# Battery_Monitoring_V4.net
KiCad netlist of a schematic drawn in EAGLE
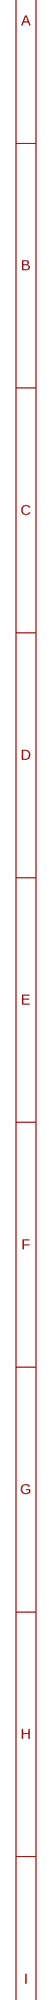
[diagram p0: schematic, sheet 1, part 1 of 2]
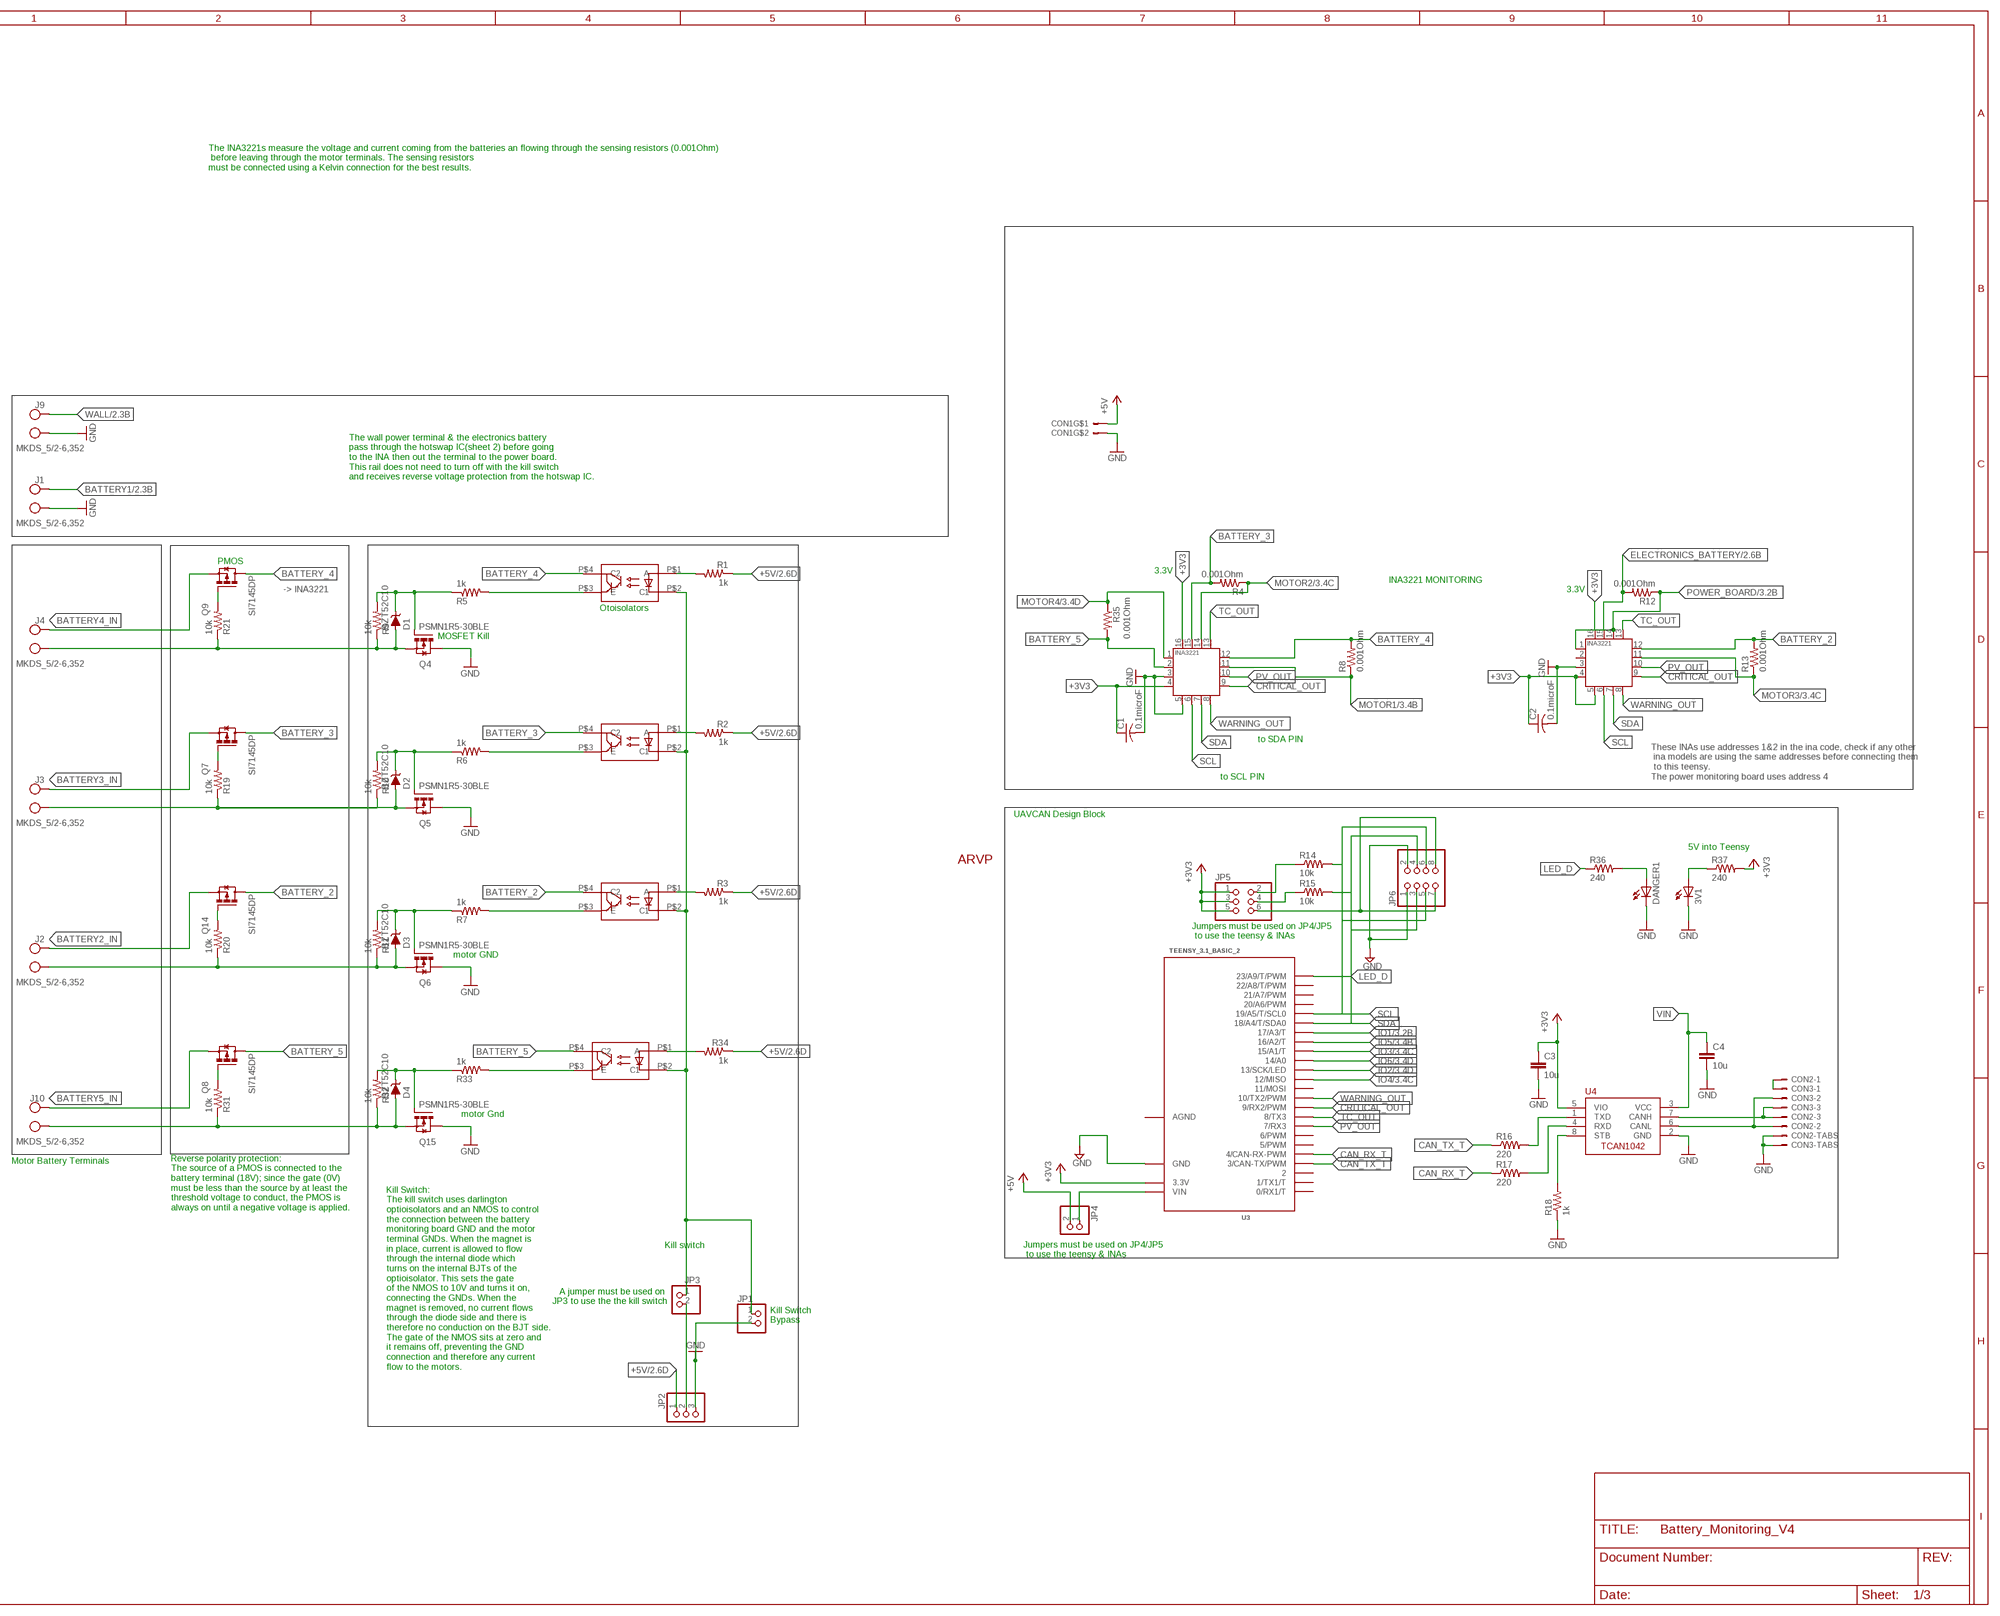
[diagram p1: schematic, sheet 1, part 2 of 2]
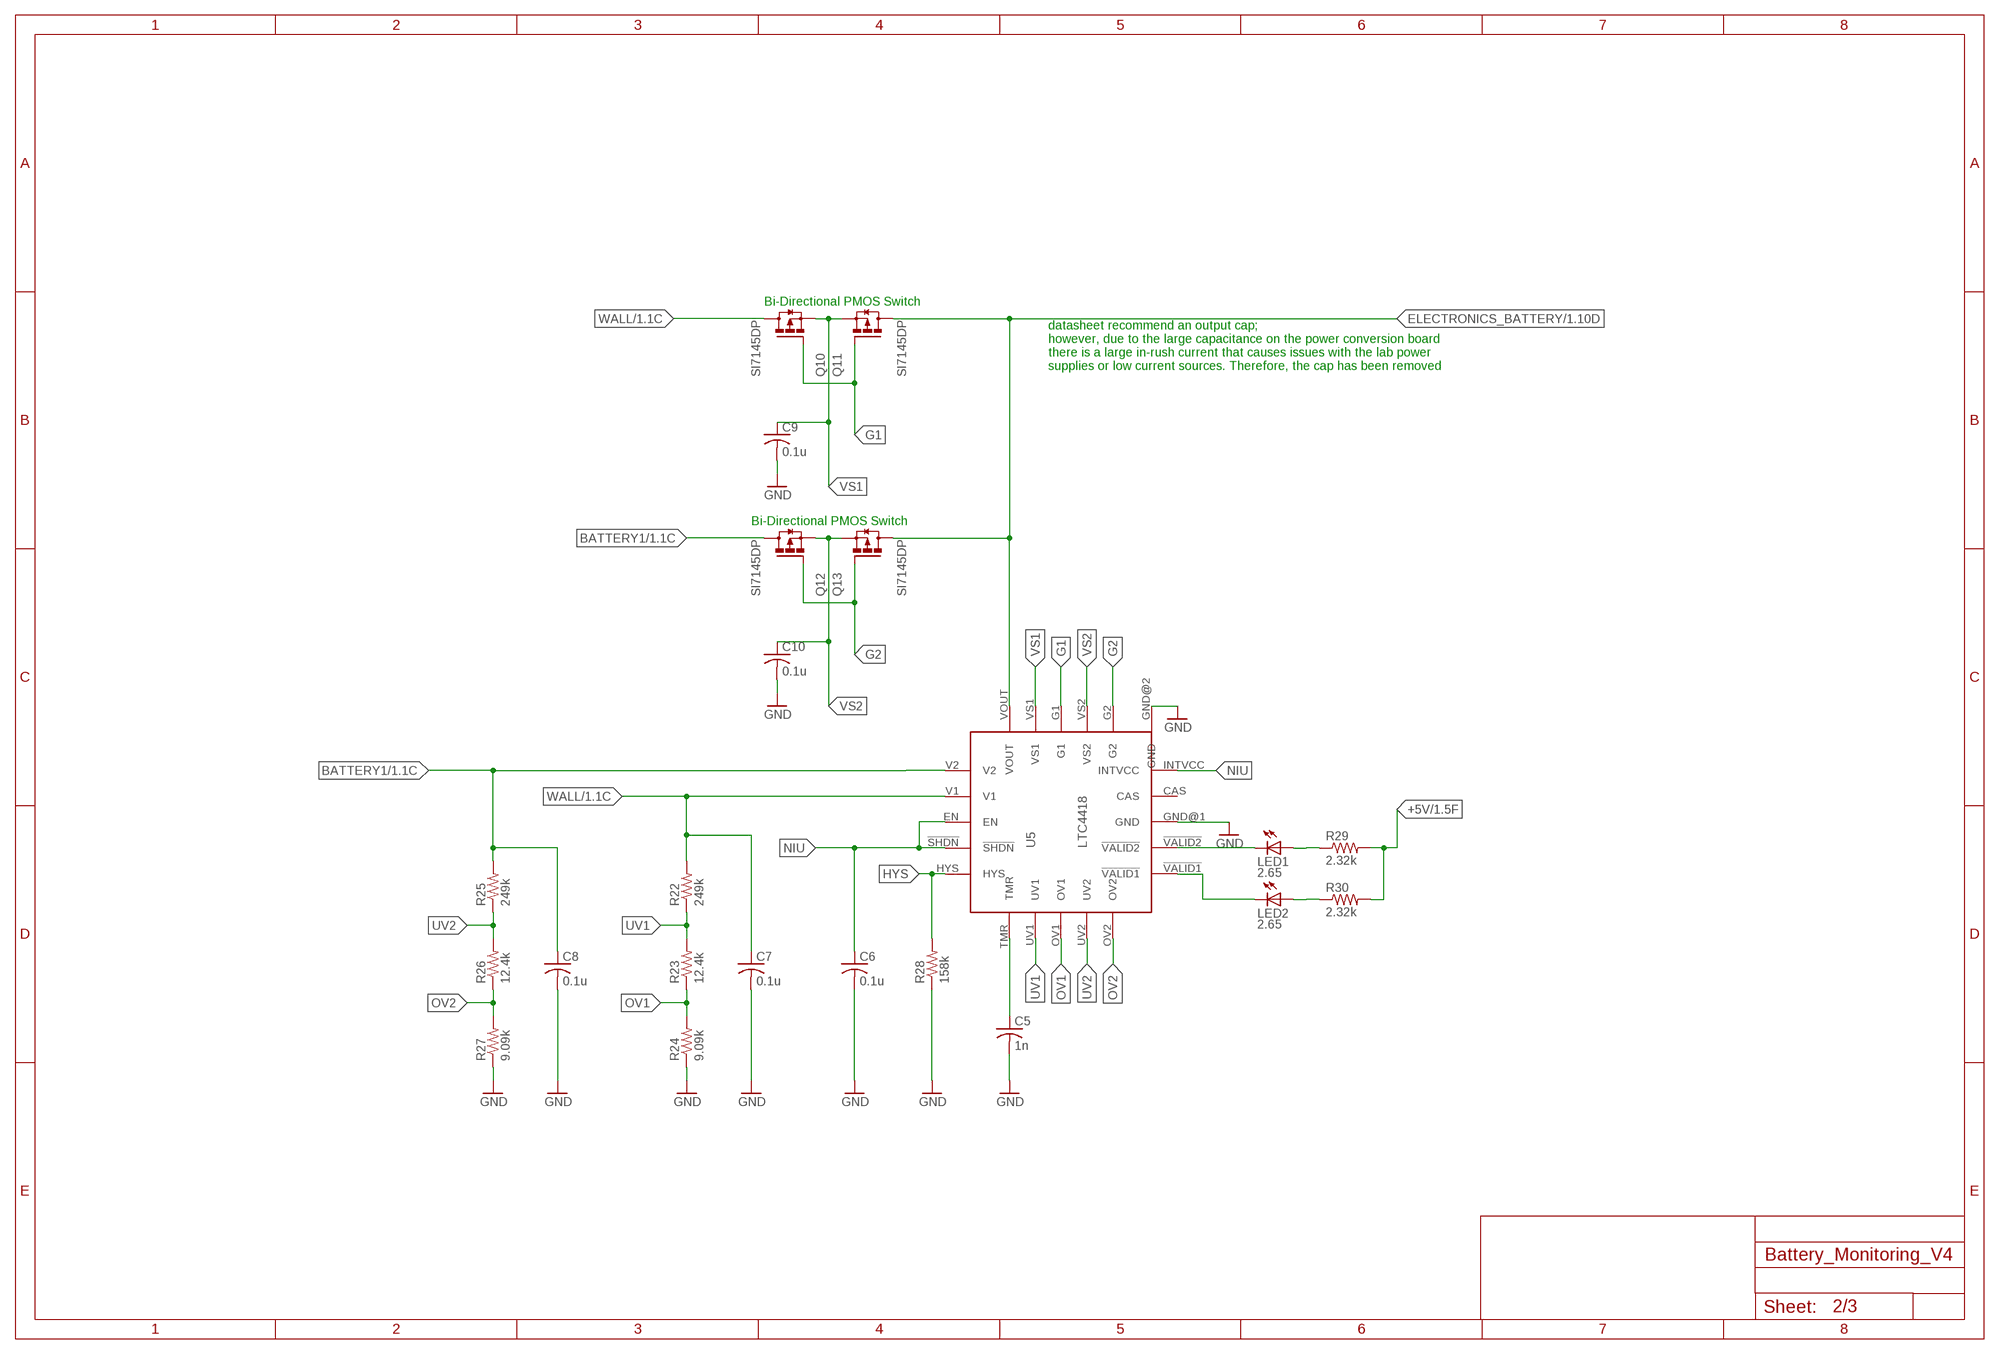
[diagram p2: schematic, sheet 2]
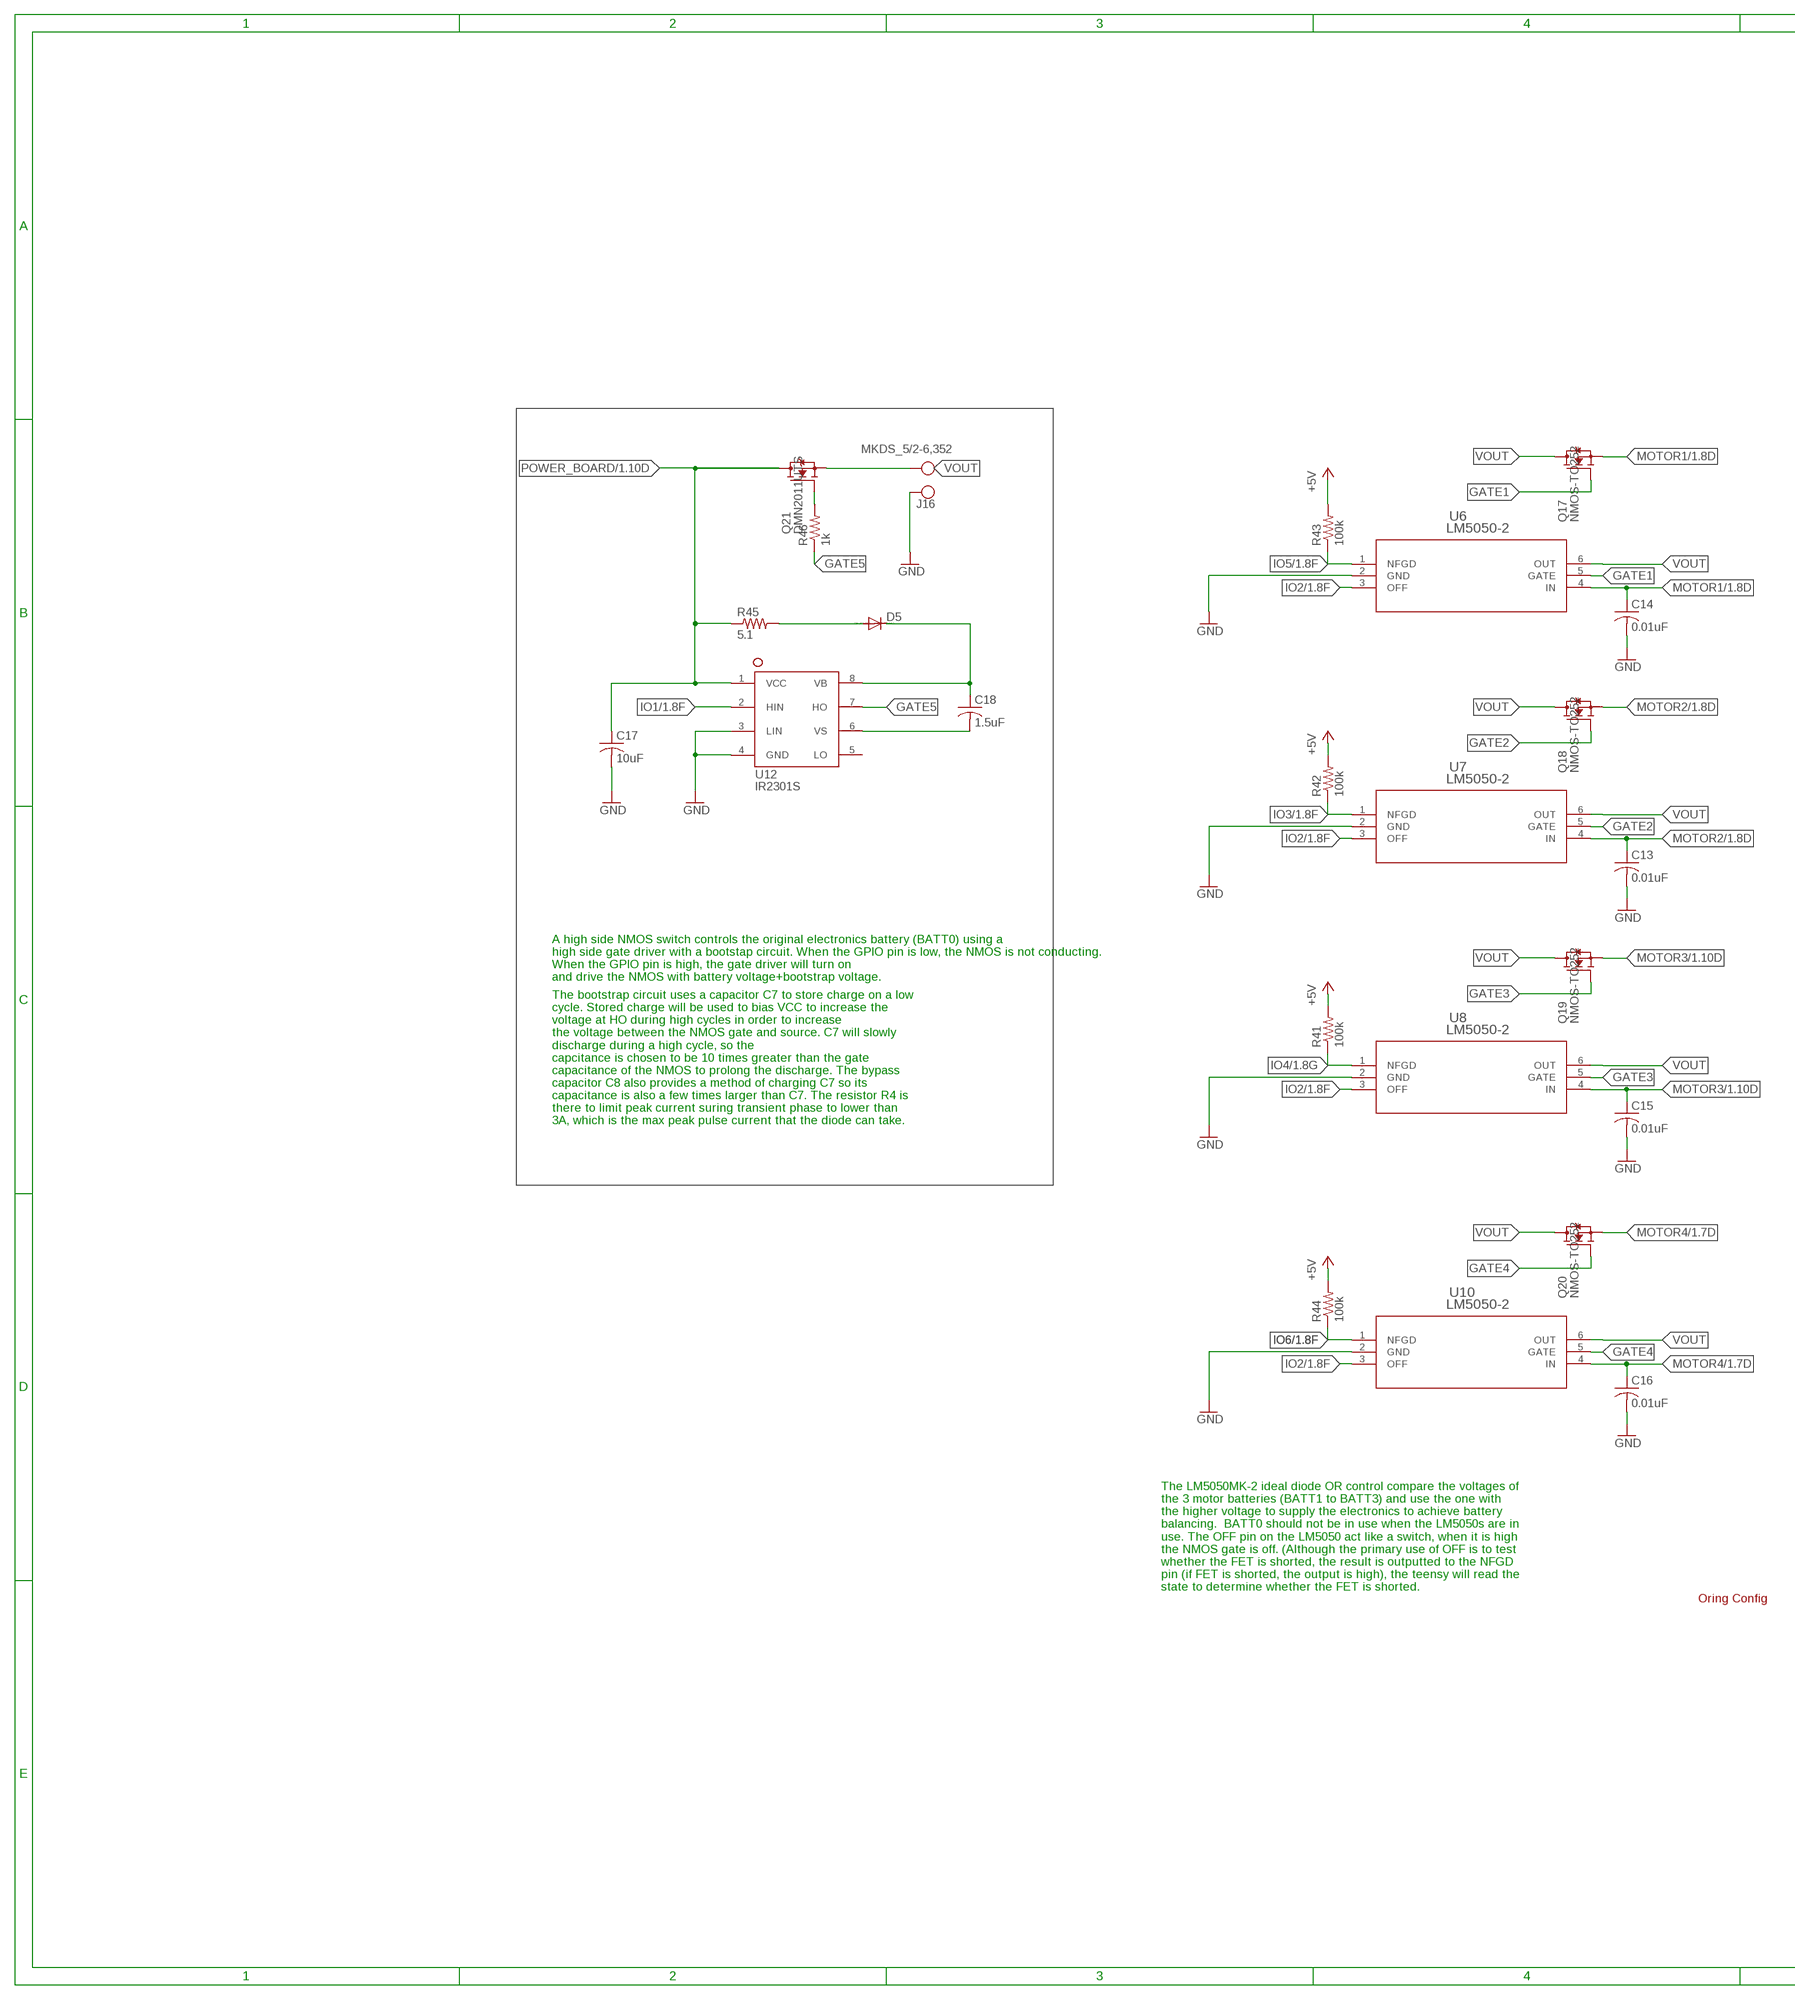
[diagram p3: schematic, sheet 3, part 1 of 2]
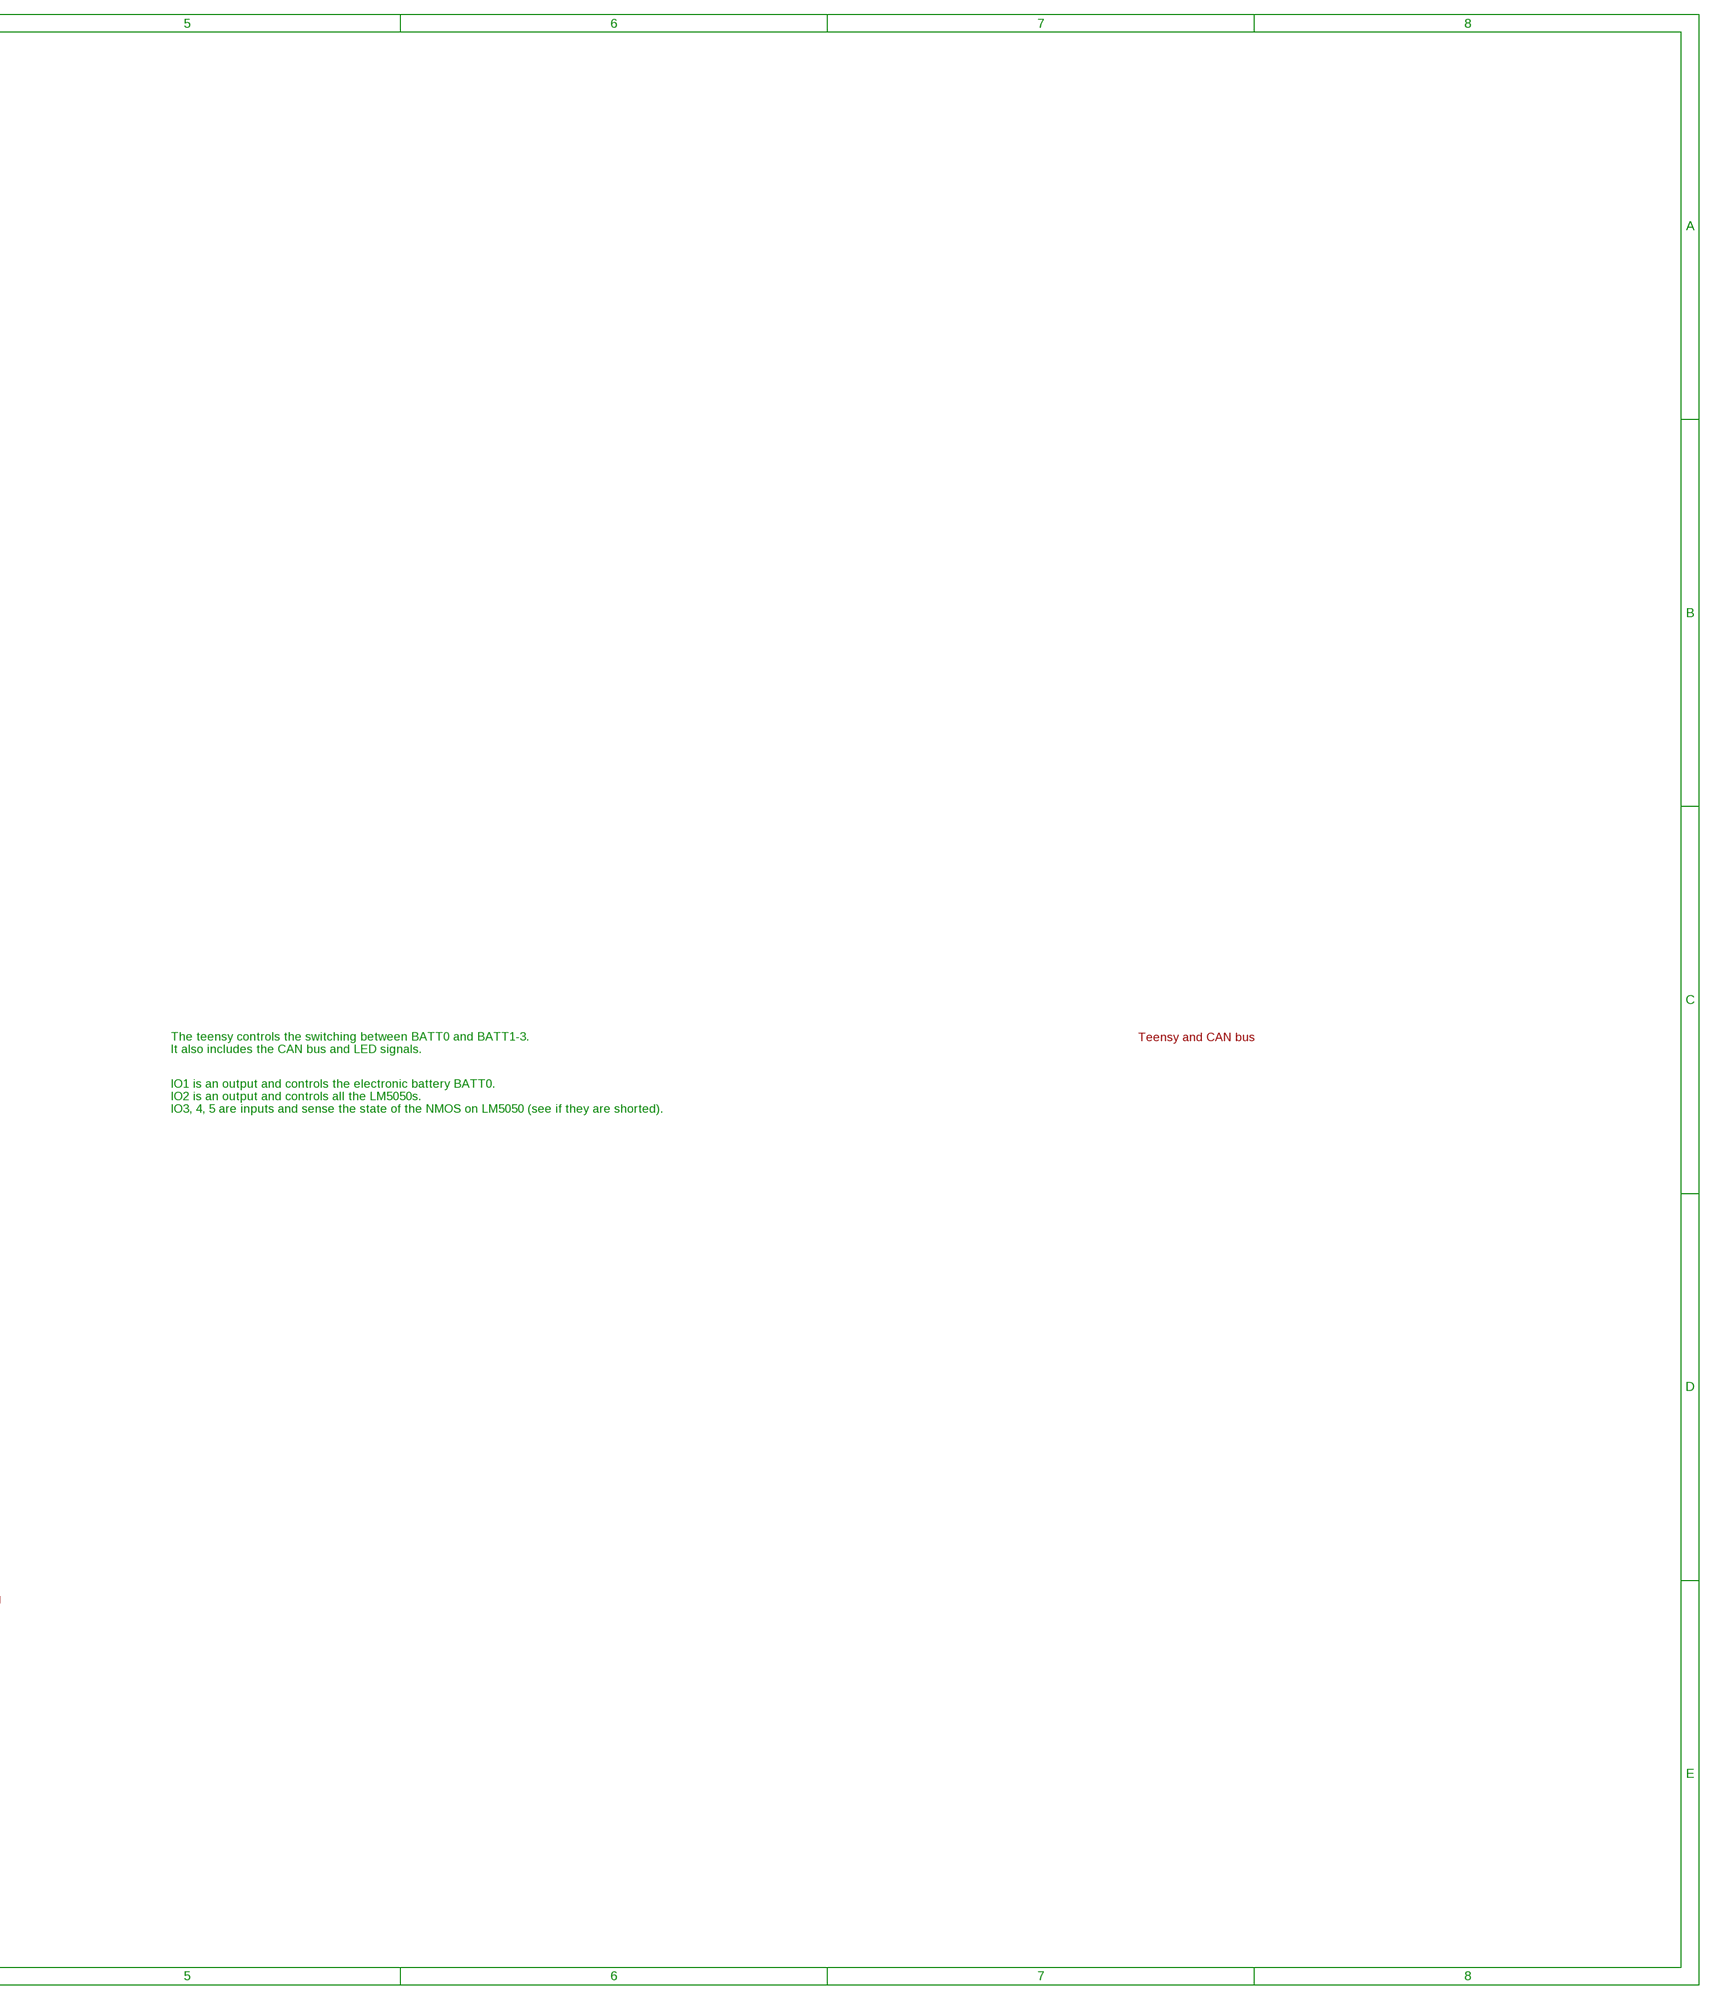
[diagram p4: schematic, sheet 3, part 2 of 2]

(export (version "E")
  (design (tool "Eeschema 10.0.6"))
  (components
    (comp (ref "3V1")
      (value "LEDSMT1206")
      (footprint "eagle-import:1206")
      (libsource (lib "eagle-import") (part "LEDSMT1206"))
    )
    (comp (ref "ARVP1")
      (value "ARVP_LOGO")
      (footprint "eagle-import:ARVP")
      (libsource (lib "eagle-import") (part "ARVP_LOGO"))
    )
    (comp (ref "C1")
      (value "0.1microF")
      (footprint "eagle-import:C2012")
      (libsource (lib "eagle-import") (part "resistor_348_C-USC2012"))
    )
    (comp (ref "C2")
      (value "0.1microF")
      (footprint "eagle-import:C2012")
      (libsource (lib "eagle-import") (part "resistor_348_C-USC2012"))
    )
    (comp (ref "C3")
      (value "10u")
      (footprint "eagle-import:C0805")
      (libsource (lib "eagle-import") (part "C-EUC0805"))
    )
    (comp (ref "C4")
      (value "10u")
      (footprint "eagle-import:C0805")
      (libsource (lib "eagle-import") (part "C-EUC0805"))
    )
    (comp (ref "CON1")
      (value "MOLEX_5566-2")
      (footprint "eagle-import:5566-2")
      (libsource (lib "eagle-import") (part "MOLEX_5566-2"))
    )
    (comp (ref "CON2")
      (value "SM03B-GHS-TB")
      (footprint "eagle-import:SM03B-GHS-TB")
      (libsource (lib "eagle-import") (part "SM03B-GHS-TB"))
    )
    (comp (ref "CON3")
      (value "SM03B-GHS-TB")
      (footprint "eagle-import:SM03B-GHS-TB")
      (libsource (lib "eagle-import") (part "SM03B-GHS-TB"))
    )
    (comp (ref "D1")
      (value "BZT52C10")
      (footprint "eagle-import:SOD-123")
      (libsource (lib "eagle-import") (part "BZT52C10"))
    )
    (comp (ref "D2")
      (value "BZT52C10")
      (footprint "eagle-import:SOD-123")
      (libsource (lib "eagle-import") (part "BZT52C10"))
    )
    (comp (ref "D3")
      (value "BZT52C10")
      (footprint "eagle-import:SOD-123")
      (libsource (lib "eagle-import") (part "BZT52C10"))
    )
    (comp (ref "D4")
      (value "BZT52C10")
      (footprint "eagle-import:SOD-123")
      (libsource (lib "eagle-import") (part "BZT52C10"))
    )
    (comp (ref "DANGER1")
      (value "LEDSMT1206")
      (footprint "eagle-import:1206")
      (libsource (lib "eagle-import") (part "LEDSMT1206"))
    )
    (comp (ref "J1")
      (value "MKDS_5/2-6,352")
      (footprint "eagle-import:MKDS_5_2-6,35")
      (libsource (lib "eagle-import") (part "MKDS_5/2-6,352"))
    )
    (comp (ref "J2")
      (value "MKDS_5/2-6,352")
      (footprint "eagle-import:MKDS_5_2-6,35")
      (libsource (lib "eagle-import") (part "MKDS_5/2-6,352"))
    )
    (comp (ref "J3")
      (value "MKDS_5/2-6,352")
      (footprint "eagle-import:MKDS_5_2-6,35")
      (libsource (lib "eagle-import") (part "MKDS_5/2-6,352"))
    )
    (comp (ref "J4")
      (value "MKDS_5/2-6,352")
      (footprint "eagle-import:MKDS_5_2-6,35")
      (libsource (lib "eagle-import") (part "MKDS_5/2-6,352"))
    )
    (comp (ref "J9")
      (value "MKDS_5/2-6,352")
      (footprint "eagle-import:MKDS_5_2-6,35")
      (libsource (lib "eagle-import") (part "MKDS_5/2-6,352"))
    )
    (comp (ref "J10")
      (value "MKDS_5/2-6,352")
      (footprint "eagle-import:MKDS_5_2-6,35")
      (libsource (lib "eagle-import") (part "MKDS_5/2-6,352"))
    )
    (comp (ref "JP1")
      (value "PINHD-1X2")
      (footprint "eagle-import:1X02")
      (libsource (lib "eagle-import") (part "PINHD-1X2"))
    )
    (comp (ref "JP2")
      (value "PINHD-1X3")
      (footprint "eagle-import:1X03")
      (libsource (lib "eagle-import") (part "PINHD-1X3"))
    )
    (comp (ref "JP3")
      (value "PINHD-1X2")
      (footprint "eagle-import:1X02")
      (libsource (lib "eagle-import") (part "PINHD-1X2"))
    )
    (comp (ref "JP4")
      (value "PINHD-1X2")
      (footprint "eagle-import:1X02")
      (libsource (lib "eagle-import") (part "PINHD-1X2"))
    )
    (comp (ref "JP5")
      (value "PINHD-2X3")
      (footprint "eagle-import:2X03")
      (libsource (lib "eagle-import") (part "PINHD-2X3"))
    )
    (comp (ref "JP6")
      (value "PINHD-2X4")
      (footprint "eagle-import:2X04")
      (libsource (lib "eagle-import") (part "PINHD-2X4"))
    )
    (comp (ref "Q1")
      (value "TCLD1000CT")
      (footprint "eagle-import:SOP-4L")
      (fields (field (name "SPICEPREFIX") "E"))
      (libsource (lib "eagle-import") (part "TCLD1000CT"))
    )
    (comp (ref "Q2")
      (value "TCLD1000CT")
      (footprint "eagle-import:SOP-4L")
      (libsource (lib "eagle-import") (part "TCLD1000CT"))
    )
    (comp (ref "Q3")
      (value "TCLD1000CT")
      (footprint "eagle-import:SOP-4L")
      (libsource (lib "eagle-import") (part "TCLD1000CT"))
    )
    (comp (ref "Q4")
      (value "PSMN1R5-30BLE")
      (footprint "eagle-import:SOT404_D2PAK")
      (libsource (lib "eagle-import") (part "PSMN1R5-30BLE"))
    )
    (comp (ref "Q5")
      (value "PSMN1R5-30BLE")
      (footprint "eagle-import:SOT404_D2PAK")
      (libsource (lib "eagle-import") (part "PSMN1R5-30BLE"))
    )
    (comp (ref "Q6")
      (value "PSMN1R5-30BLE")
      (footprint "eagle-import:SOT404_D2PAK")
      (libsource (lib "eagle-import") (part "PSMN1R5-30BLE"))
    )
    (comp (ref "Q7")
      (value "SI7145DP")
      (footprint "eagle-import:SO-8_PPAK_TEST")
      (fields (field (name "MPN") "SI7145DP-T1-GE3"))
      (libsource (lib "eagle-import") (part "Si7145DP_SI7145DP"))
    )
    (comp (ref "Q8")
      (value "SI7145DP")
      (footprint "eagle-import:SO-8_PPAK_TEST")
      (fields (field (name "MPN") "SI7145DP-T1-GE3"))
      (libsource (lib "eagle-import") (part "Si7145DP_SI7145DP"))
    )
    (comp (ref "Q9")
      (value "SI7145DP")
      (footprint "eagle-import:SO-8_PPAK_TEST")
      (fields (field (name "MPN") "SI7145DP-T1-GE3"))
      (libsource (lib "eagle-import") (part "Si7145DP_SI7145DP"))
    )
    (comp (ref "Q14")
      (value "SI7145DP")
      (footprint "eagle-import:SO-8_PPAK_TEST")
      (fields (field (name "MPN") "SI7145DP-T1-GE3"))
      (libsource (lib "eagle-import") (part "Si7145DP_SI7145DP"))
    )
    (comp (ref "Q15")
      (value "PSMN1R5-30BLE")
      (footprint "eagle-import:SOT404_D2PAK")
      (libsource (lib "eagle-import") (part "PSMN1R5-30BLE"))
    )
    (comp (ref "Q16")
      (value "TCLD1000CT")
      (footprint "eagle-import:SOP-4L")
      (libsource (lib "eagle-import") (part "TCLD1000CT"))
    )
    (comp (ref "R1")
      (value "1k")
      (footprint "eagle-import:R0805")
      (libsource (lib "eagle-import") (part "adafruit_420_R-US_R0805"))
    )
    (comp (ref "R2")
      (value "1k")
      (footprint "eagle-import:R0805")
      (libsource (lib "eagle-import") (part "adafruit_420_R-US_R0805"))
    )
    (comp (ref "R3")
      (value "1k")
      (footprint "eagle-import:R0805")
      (libsource (lib "eagle-import") (part "adafruit_420_R-US_R0805"))
    )
    (comp (ref "R4")
      (value "0.001Ohm")
      (footprint "eagle-import:3920")
      (libsource (lib "eagle-import") (part "HCS3920FT1L00"))
    )
    (comp (ref "R5")
      (value "1k")
      (footprint "eagle-import:M1206")
      (libsource (lib "eagle-import") (part "adafruit_420_R-US_M1206"))
    )
    (comp (ref "R6")
      (value "1k")
      (footprint "eagle-import:M1206")
      (libsource (lib "eagle-import") (part "adafruit_420_R-US_M1206"))
    )
    (comp (ref "R7")
      (value "1k")
      (footprint "eagle-import:M1206")
      (libsource (lib "eagle-import") (part "adafruit_420_R-US_M1206"))
    )
    (comp (ref "R8")
      (value "0.001Ohm")
      (footprint "eagle-import:3920")
      (libsource (lib "eagle-import") (part "HCS3920FT1L00"))
    )
    (comp (ref "R9")
      (value "10k")
      (footprint "eagle-import:M1206")
      (libsource (lib "eagle-import") (part "adafruit_420_R-US_M1206"))
    )
    (comp (ref "R10")
      (value "10k")
      (footprint "eagle-import:M1206")
      (libsource (lib "eagle-import") (part "adafruit_420_R-US_M1206"))
    )
    (comp (ref "R11")
      (value "10k")
      (footprint "eagle-import:M1206")
      (libsource (lib "eagle-import") (part "adafruit_420_R-US_M1206"))
    )
    (comp (ref "R12")
      (value "0.001Ohm")
      (footprint "eagle-import:3920")
      (libsource (lib "eagle-import") (part "HCS3920FT1L00"))
    )
    (comp (ref "R13")
      (value "0.001Ohm")
      (footprint "eagle-import:3920")
      (libsource (lib "eagle-import") (part "HCS3920FT1L00"))
    )
    (comp (ref "R14")
      (value "10k")
      (footprint "eagle-import:R1206")
      (libsource (lib "eagle-import") (part "rcl_334_R-US_R1206"))
    )
    (comp (ref "R15")
      (value "10k")
      (footprint "eagle-import:R1206")
      (libsource (lib "eagle-import") (part "rcl_334_R-US_R1206"))
    )
    (comp (ref "R16")
      (value "220")
      (footprint "eagle-import:R0805")
      (libsource (lib "eagle-import") (part "rcl_334_R-US_R0805"))
    )
    (comp (ref "R17")
      (value "220")
      (footprint "eagle-import:R0805")
      (libsource (lib "eagle-import") (part "rcl_334_R-US_R0805"))
    )
    (comp (ref "R18")
      (value "1k")
      (footprint "eagle-import:R0805")
      (libsource (lib "eagle-import") (part "rcl_334_R-US_R0805"))
    )
    (comp (ref "R19")
      (value "10k")
      (footprint "eagle-import:M1206")
      (fields (field (name "MPN") "RC0603FR-0710KL"))
      (libsource (lib "eagle-import") (part "R-US_M1206"))
    )
    (comp (ref "R20")
      (value "10k")
      (footprint "eagle-import:M1206")
      (fields (field (name "MPN") "RC0603FR-0710KL"))
      (libsource (lib "eagle-import") (part "R-US_M1206"))
    )
    (comp (ref "R21")
      (value "10k")
      (footprint "eagle-import:M1206")
      (fields (field (name "MPN") "RC0603FR-0710KL"))
      (libsource (lib "eagle-import") (part "adafruit_420_R-US_M1206"))
    )
    (comp (ref "R31")
      (value "10k")
      (footprint "eagle-import:M1206")
      (fields (field (name "MPN") "RC0603FR-0710KL"))
      (libsource (lib "eagle-import") (part "R-US_M1206"))
    )
    (comp (ref "R32")
      (value "10k")
      (footprint "eagle-import:M1206")
      (libsource (lib "eagle-import") (part "adafruit_420_R-US_M1206"))
    )
    (comp (ref "R33")
      (value "1k")
      (footprint "eagle-import:M1206")
      (libsource (lib "eagle-import") (part "adafruit_420_R-US_M1206"))
    )
    (comp (ref "R34")
      (value "1k")
      (footprint "eagle-import:R0805")
      (libsource (lib "eagle-import") (part "adafruit_420_R-US_R0805"))
    )
    (comp (ref "R35")
      (value "0.001Ohm")
      (footprint "eagle-import:3920")
      (libsource (lib "eagle-import") (part "HCS3920FT1L00"))
    )
    (comp (ref "R36")
      (value "240")
      (footprint "eagle-import:R1206")
      (libsource (lib "eagle-import") (part "resistor_348_R-US_R1206"))
    )
    (comp (ref "R37")
      (value "240")
      (footprint "eagle-import:R1206")
      (libsource (lib "eagle-import") (part "resistor_348_R-US_R1206"))
    )
    (comp (ref "U1")
      (value "INA3221.")
      (footprint "eagle-import:HVQFN16_4X4")
      (libsource (lib "eagle-import") (part "INA3221."))
    )
    (comp (ref "U2")
      (value "INA3221.")
      (footprint "eagle-import:HVQFN16_4X4")
      (libsource (lib "eagle-import") (part "INA3221."))
    )
    (comp (ref "U3")
      (value "TEENSY_3.1_BASIC_2")
      (footprint "eagle-import:TEENSY_3.1_BASIC_2")
      (libsource (lib "eagle-import") (part "TEENSY_3.1_BASIC_2"))
    )
    (comp (ref "U4")
      (value "TCAN1042HVDR")
      (footprint "eagle-import:SO-8")
      (libsource (lib "eagle-import") (part "TCAN1042HVDR"))
    )
    (comp (ref "C5")
      (value "1n")
      (footprint "eagle-import:C0805")
      (libsource (lib "eagle-import") (part "C-USC0805"))
    )
    (comp (ref "C6")
      (value "0.1u")
      (footprint "eagle-import:C0805")
      (libsource (lib "eagle-import") (part "C-USC0805"))
    )
    (comp (ref "C7")
      (value "0.1u")
      (footprint "eagle-import:C0805")
      (libsource (lib "eagle-import") (part "C-USC0805"))
    )
    (comp (ref "C8")
      (value "0.1u")
      (footprint "eagle-import:C0805")
      (libsource (lib "eagle-import") (part "C-USC0805"))
    )
    (comp (ref "C9")
      (value "0.1u")
      (footprint "eagle-import:C0805")
      (libsource (lib "eagle-import") (part "C-USC0805"))
    )
    (comp (ref "C10")
      (value "0.1u")
      (footprint "eagle-import:C0805")
      (libsource (lib "eagle-import") (part "C-USC0805"))
    )
    (comp (ref "LED1")
      (value "2.65")
      (footprint "eagle-import:SML0805")
      (libsource (lib "eagle-import") (part "LEDSML0805"))
    )
    (comp (ref "LED2")
      (value "2.65")
      (footprint "eagle-import:SML0805")
      (libsource (lib "eagle-import") (part "LEDSML0805"))
    )
    (comp (ref "Q10")
      (value "SI7145DP")
      (footprint "eagle-import:SO-8_PPAK_TEST")
      (libsource (lib "eagle-import") (part "SI7145DP"))
    )
    (comp (ref "Q11")
      (value "SI7145DP")
      (footprint "eagle-import:SO-8_PPAK_TEST")
      (libsource (lib "eagle-import") (part "SI7145DP"))
    )
    (comp (ref "Q12")
      (value "SI7145DP")
      (footprint "eagle-import:SO-8_PPAK_TEST")
      (libsource (lib "eagle-import") (part "SI7145DP"))
    )
    (comp (ref "Q13")
      (value "SI7145DP")
      (footprint "eagle-import:SO-8_PPAK_TEST")
      (libsource (lib "eagle-import") (part "SI7145DP"))
    )
    (comp (ref "R22")
      (value "249k")
      (footprint "eagle-import:R1206")
      (libsource (lib "eagle-import") (part "adafruit_420_R-US_R1206"))
    )
    (comp (ref "R23")
      (value "12.4k")
      (footprint "eagle-import:R0805")
      (libsource (lib "eagle-import") (part "adafruit_420_R-US_R0805"))
    )
    (comp (ref "R24")
      (value "9.09k")
      (footprint "eagle-import:R0805")
      (libsource (lib "eagle-import") (part "adafruit_420_R-US_R0805"))
    )
    (comp (ref "R25")
      (value "249k")
      (footprint "eagle-import:R1206")
      (libsource (lib "eagle-import") (part "adafruit_420_R-US_R1206"))
    )
    (comp (ref "R26")
      (value "12.4k")
      (footprint "eagle-import:R0805")
      (libsource (lib "eagle-import") (part "adafruit_420_R-US_R0805"))
    )
    (comp (ref "R27")
      (value "9.09k")
      (footprint "eagle-import:R0805")
      (libsource (lib "eagle-import") (part "adafruit_420_R-US_R0805"))
    )
    (comp (ref "R28")
      (value "158k")
      (footprint "eagle-import:R0805")
      (libsource (lib "eagle-import") (part "adafruit_420_R-US_R0805"))
    )
    (comp (ref "R29")
      (value "2.32k")
      (footprint "eagle-import:R0805")
      (libsource (lib "eagle-import") (part "adafruit_420_R-US_R0805"))
    )
    (comp (ref "R30")
      (value "2.32k")
      (footprint "eagle-import:R0805")
      (libsource (lib "eagle-import") (part "adafruit_420_R-US_R0805"))
    )
    (comp (ref "U5")
      (value "LTC4418")
      (footprint "eagle-import:20-QFN(4X4)")
      (libsource (lib "eagle-import") (part "LTC4418"))
    )
    (comp (ref "C13")
      (value "0.01uF")
      (footprint "eagle-import:C0805")
      (libsource (lib "eagle-import") (part "C-USC0805"))
    )
    (comp (ref "C14")
      (value "0.01uF")
      (footprint "eagle-import:C0805")
      (libsource (lib "eagle-import") (part "C-USC0805"))
    )
    (comp (ref "C15")
      (value "0.01uF")
      (footprint "eagle-import:C0805")
      (libsource (lib "eagle-import") (part "C-USC0805"))
    )
    (comp (ref "C16")
      (value "0.01uF")
      (footprint "eagle-import:C0805")
      (libsource (lib "eagle-import") (part "C-USC0805"))
    )
    (comp (ref "C17")
      (value "10uF")
      (footprint "eagle-import:C1206")
      (libsource (lib "eagle-import") (part "C-USC1206"))
    )
    (comp (ref "C18")
      (value "1.5uF")
      (footprint "eagle-import:C0805")
      (libsource (lib "eagle-import") (part "C-USC0805"))
    )
    (comp (ref "D5")
      (value "DIODE-DO-214AC")
      (footprint "eagle-import:DO-214AC")
      (libsource (lib "eagle-import") (part "DIODE-DO-214AC"))
    )
    (comp (ref "J16")
      (value "MKDS_5/2-6,352")
      (footprint "eagle-import:MKDS_5_2-6,35")
      (libsource (lib "eagle-import") (part "MKDS_5/2-6,352"))
    )
    (comp (ref "Q17")
      (value "NMOS-TO252")
      (footprint "eagle-import:TO252")
      (libsource (lib "eagle-import") (part "NMOS-TO252"))
    )
    (comp (ref "Q18")
      (value "NMOS-TO252")
      (footprint "eagle-import:TO252")
      (libsource (lib "eagle-import") (part "NMOS-TO252"))
    )
    (comp (ref "Q19")
      (value "NMOS-TO252")
      (footprint "eagle-import:TO252")
      (libsource (lib "eagle-import") (part "NMOS-TO252"))
    )
    (comp (ref "Q20")
      (value "NMOS-TO252")
      (footprint "eagle-import:TO252")
      (libsource (lib "eagle-import") (part "NMOS-TO252"))
    )
    (comp (ref "Q21")
      (value "DMN2011UTS")
      (footprint "eagle-import:SOP65P640X120-8N")
      (libsource (lib "eagle-import") (part "DMN2011UTS"))
    )
    (comp (ref "R41")
      (value "100k")
      (footprint "eagle-import:R1206")
      (libsource (lib "eagle-import") (part "adafruit_420_R-US_R1206"))
    )
    (comp (ref "R42")
      (value "100k")
      (footprint "eagle-import:R1206")
      (libsource (lib "eagle-import") (part "adafruit_420_R-US_R1206"))
    )
    (comp (ref "R43")
      (value "100k")
      (footprint "eagle-import:R1206")
      (libsource (lib "eagle-import") (part "adafruit_420_R-US_R1206"))
    )
    (comp (ref "R44")
      (value "100k")
      (footprint "eagle-import:R1206")
      (libsource (lib "eagle-import") (part "adafruit_420_R-US_R1206"))
    )
    (comp (ref "R45")
      (value "5.1")
      (footprint "eagle-import:R1206")
      (libsource (lib "eagle-import") (part "adafruit_420_R-US_R1206"))
    )
    (comp (ref "R46")
      (value "1k")
      (footprint "eagle-import:R0805")
      (libsource (lib "eagle-import") (part "rcl_334_R-US_R0805"))
    )
    (comp (ref "U6")
      (value "LM5050-2")
      (footprint "eagle-import:MK06A")
      (libsource (lib "eagle-import") (part "LM5050-2"))
    )
    (comp (ref "U7")
      (value "LM5050-2")
      (footprint "eagle-import:MK06A")
      (libsource (lib "eagle-import") (part "LM5050-2"))
    )
    (comp (ref "U8")
      (value "LM5050-2")
      (footprint "eagle-import:MK06A")
      (libsource (lib "eagle-import") (part "LM5050-2"))
    )
    (comp (ref "U10")
      (value "LM5050-2")
      (footprint "eagle-import:MK06A")
      (libsource (lib "eagle-import") (part "LM5050-2"))
    )
    (comp (ref "U12")
      (value "IR2301S")
      (footprint "eagle-import:SOIC8")
      (libsource (lib "eagle-import") (part "IR2301S"))
    )
  )
  (nets
    (net (code "1") (name "+3V3") (class "Default")
      (node (ref "C1") (pin "1") (pinfunction "1_1") (pintype "passive"))
      (node (ref "C2") (pin "1") (pinfunction "1_1") (pintype "passive"))
      (node (ref "C3") (pin "1") (pinfunction "1_1") (pintype "passive"))
      (node (ref "JP5") (pin "1") (pinfunction "1_1") (pintype "passive"))
      (node (ref "JP5") (pin "3") (pinfunction "3_3") (pintype "passive"))
      (node (ref "JP5") (pin "5") (pinfunction "5_5") (pintype "passive"))
      (node (ref "R37") (pin "2") (pinfunction "2_2") (pintype "passive"))
      (node (ref "U1") (pin "16") (pinfunction "VPU_16") (pintype "input"))
      (node (ref "U1") (pin "4") (pinfunction "VS_4") (pintype "power_in"))
      (node (ref "U2") (pin "16") (pinfunction "VPU_16") (pintype "input"))
      (node (ref "U2") (pin "4") (pinfunction "VS_4") (pintype "power_in"))
      (node (ref "U2") (pin "5") (pinfunction "A0_5") (pintype "input"))
      (node (ref "U3") (pin "3.3V") (pinfunction "3.3V_3.3V") (pintype "power_in"))
      (node (ref "U4") (pin "5") (pinfunction "VIO_5") (pintype "bidirectional"))
    )
    (net (code "2") (name "+5V") (class "Default")
      (node (ref "CON1") (pin "1") (pinfunction "S_1") (pintype "passive"))
      (node (ref "JP2") (pin "1") (pinfunction "1_1") (pintype "passive"))
      (node (ref "JP4") (pin "2") (pinfunction "2_2") (pintype "passive"))
      (node (ref "R1") (pin "1") (pinfunction "1_1") (pintype "passive"))
      (node (ref "R2") (pin "1") (pinfunction "1_1") (pintype "passive"))
      (node (ref "R29") (pin "2") (pinfunction "2_2") (pintype "passive"))
      (node (ref "R3") (pin "1") (pinfunction "1_1") (pintype "passive"))
      (node (ref "R30") (pin "2") (pinfunction "2_2") (pintype "passive"))
      (node (ref "R34") (pin "1") (pinfunction "1_1") (pintype "passive"))
      (node (ref "R41") (pin "2") (pinfunction "2_2") (pintype "passive"))
      (node (ref "R42") (pin "2") (pinfunction "2_2") (pintype "passive"))
      (node (ref "R43") (pin "2") (pinfunction "2_2") (pintype "passive"))
      (node (ref "R44") (pin "2") (pinfunction "2_2") (pintype "passive"))
    )
    (net (code "3") (name "AGND") (class "Default")
      (node (ref "U3") (pin "AGND") (pinfunction "AGND_AGND") (pintype "power_in"))
    )
    (net (code "4") (name "BATTERY1") (class "Default")
      (node (ref "C8") (pin "1") (pinfunction "1_1") (pintype "passive"))
      (node (ref "J1") (pin "2") (pinfunction "KL1_2") (pintype "passive"))
      (node (ref "Q12") (pin "D@1") (pinfunction "D_D@1") (pintype "passive"))
      (node (ref "Q12") (pin "D@2") (pinfunction "D_D@2") (pintype "passive"))
      (node (ref "Q12") (pin "D@3") (pinfunction "D_D@3") (pintype "passive"))
      (node (ref "Q12") (pin "D@4") (pinfunction "D_D@4") (pintype "passive"))
      (node (ref "Q12") (pin "D@5") (pinfunction "D_D@5") (pintype "passive"))
      (node (ref "R25") (pin "2") (pinfunction "2_2") (pintype "passive"))
      (node (ref "U5") (pin "V2") (pinfunction "V2_V2") (pintype "bidirectional"))
    )
    (net (code "5") (name "BATTERY2_IN") (class "Default")
      (node (ref "J2") (pin "2") (pinfunction "KL1_2") (pintype "passive"))
      (node (ref "Q14") (pin "S@1") (pinfunction "S_S@1") (pintype "passive"))
      (node (ref "Q14") (pin "S@2") (pinfunction "S_S@2") (pintype "passive"))
      (node (ref "Q14") (pin "S@3") (pinfunction "S_S@3") (pintype "passive"))
    )
    (net (code "6") (name "BATTERY3_IN") (class "Default")
      (node (ref "J3") (pin "2") (pinfunction "KL1_2") (pintype "passive"))
      (node (ref "Q7") (pin "S@1") (pinfunction "S_S@1") (pintype "passive"))
      (node (ref "Q7") (pin "S@2") (pinfunction "S_S@2") (pintype "passive"))
      (node (ref "Q7") (pin "S@3") (pinfunction "S_S@3") (pintype "passive"))
    )
    (net (code "7") (name "BATTERY4_IN") (class "Default")
      (node (ref "J4") (pin "2") (pinfunction "KL1_2") (pintype "passive"))
      (node (ref "Q9") (pin "S@1") (pinfunction "S_S@1") (pintype "passive"))
      (node (ref "Q9") (pin "S@2") (pinfunction "S_S@2") (pintype "passive"))
      (node (ref "Q9") (pin "S@3") (pinfunction "S_S@3") (pintype "passive"))
    )
    (net (code "8") (name "BATTERY5_IN") (class "Default")
      (node (ref "J10") (pin "2") (pinfunction "KL1_2") (pintype "passive"))
      (node (ref "Q8") (pin "S@1") (pinfunction "S_S@1") (pintype "passive"))
      (node (ref "Q8") (pin "S@2") (pinfunction "S_S@2") (pintype "passive"))
      (node (ref "Q8") (pin "S@3") (pinfunction "S_S@3") (pintype "passive"))
    )
    (net (code "9") (name "BATTERY_2") (class "Default")
      (node (ref "Q14") (pin "D@1") (pinfunction "D_D@1") (pintype "passive"))
      (node (ref "Q14") (pin "D@2") (pinfunction "D_D@2") (pintype "passive"))
      (node (ref "Q14") (pin "D@3") (pinfunction "D_D@3") (pintype "passive"))
      (node (ref "Q14") (pin "D@4") (pinfunction "D_D@4") (pintype "passive"))
      (node (ref "Q14") (pin "D@5") (pinfunction "D_D@5") (pintype "passive"))
      (node (ref "Q3") (pin "P$4") (pinfunction "C2_P$4") (pintype "bidirectional"))
      (node (ref "R13") (pin "P$2") (pinfunction "2_P$2") (pintype "passive"))
      (node (ref "U2") (pin "12") (pinfunction "IN+1_12") (pintype "input"))
    )
    (net (code "10") (name "BATTERY_3") (class "Default")
      (node (ref "Q2") (pin "P$4") (pinfunction "C2_P$4") (pintype "bidirectional"))
      (node (ref "Q7") (pin "D@1") (pinfunction "D_D@1") (pintype "passive"))
      (node (ref "Q7") (pin "D@2") (pinfunction "D_D@2") (pintype "passive"))
      (node (ref "Q7") (pin "D@3") (pinfunction "D_D@3") (pintype "passive"))
      (node (ref "Q7") (pin "D@4") (pinfunction "D_D@4") (pintype "passive"))
      (node (ref "Q7") (pin "D@5") (pinfunction "D_D@5") (pintype "passive"))
      (node (ref "R4") (pin "P$2") (pinfunction "2_P$2") (pintype "passive"))
      (node (ref "U1") (pin "15") (pinfunction "IN+2_15") (pintype "input"))
    )
    (net (code "11") (name "BATTERY_4") (class "Default")
      (node (ref "Q1") (pin "P$4") (pinfunction "C2_P$4") (pintype "bidirectional"))
      (node (ref "Q9") (pin "D@1") (pinfunction "D_D@1") (pintype "passive"))
      (node (ref "Q9") (pin "D@2") (pinfunction "D_D@2") (pintype "passive"))
      (node (ref "Q9") (pin "D@3") (pinfunction "D_D@3") (pintype "passive"))
      (node (ref "Q9") (pin "D@4") (pinfunction "D_D@4") (pintype "passive"))
      (node (ref "Q9") (pin "D@5") (pinfunction "D_D@5") (pintype "passive"))
      (node (ref "R8") (pin "P$2") (pinfunction "2_P$2") (pintype "passive"))
      (node (ref "U1") (pin "12") (pinfunction "IN+1_12") (pintype "input"))
    )
    (net (code "12") (name "BATTERY_5") (class "Default")
      (node (ref "Q16") (pin "P$4") (pinfunction "C2_P$4") (pintype "bidirectional"))
      (node (ref "Q8") (pin "D@1") (pinfunction "D_D@1") (pintype "passive"))
      (node (ref "Q8") (pin "D@2") (pinfunction "D_D@2") (pintype "passive"))
      (node (ref "Q8") (pin "D@3") (pinfunction "D_D@3") (pintype "passive"))
      (node (ref "Q8") (pin "D@4") (pinfunction "D_D@4") (pintype "passive"))
      (node (ref "Q8") (pin "D@5") (pinfunction "D_D@5") (pintype "passive"))
      (node (ref "R35") (pin "P$2") (pinfunction "2_P$2") (pintype "passive"))
      (node (ref "U1") (pin "2") (pinfunction "IN+3_2") (pintype "input"))
    )
    (net (code "13") (name "CAN_RX_T") (class "Default")
      (node (ref "R17") (pin "1") (pinfunction "1_1") (pintype "passive"))
      (node (ref "U3") (pin "4") (pinfunction "4/CAN-RX-PWM_4") (pintype "bidirectional"))
    )
    (net (code "14") (name "CAN_TX_T") (class "Default")
      (node (ref "R16") (pin "1") (pinfunction "1_1") (pintype "passive"))
      (node (ref "U3") (pin "3") (pinfunction "3/CAN-TX/PWM_3") (pintype "bidirectional"))
    )
    (net (code "15") (name "CRITICAL_OUT") (class "Default")
      (node (ref "U1") (pin "9") (pinfunction "CRITICAL_9") (pintype "output"))
      (node (ref "U2") (pin "9") (pinfunction "CRITICAL_9") (pintype "output"))
      (node (ref "U3") (pin "9") (pinfunction "9/RX2/PWM_9") (pintype "bidirectional"))
    )
    (net (code "16") (name "ELECTRONICS_BATTERY") (class "Default")
      (node (ref "Q11") (pin "D@1") (pinfunction "D_D@1") (pintype "passive"))
      (node (ref "Q11") (pin "D@2") (pinfunction "D_D@2") (pintype "passive"))
      (node (ref "Q11") (pin "D@3") (pinfunction "D_D@3") (pintype "passive"))
      (node (ref "Q11") (pin "D@4") (pinfunction "D_D@4") (pintype "passive"))
      (node (ref "Q11") (pin "D@5") (pinfunction "D_D@5") (pintype "passive"))
      (node (ref "Q13") (pin "D@1") (pinfunction "D_D@1") (pintype "passive"))
      (node (ref "Q13") (pin "D@2") (pinfunction "D_D@2") (pintype "passive"))
      (node (ref "Q13") (pin "D@3") (pinfunction "D_D@3") (pintype "passive"))
      (node (ref "Q13") (pin "D@4") (pinfunction "D_D@4") (pintype "passive"))
      (node (ref "Q13") (pin "D@5") (pinfunction "D_D@5") (pintype "passive"))
      (node (ref "R12") (pin "P$2") (pinfunction "2_P$2") (pintype "passive"))
      (node (ref "U2") (pin "15") (pinfunction "IN+2_15") (pintype "input"))
      (node (ref "U5") (pin "VOUT") (pinfunction "VOUT_VOUT") (pintype "power_in"))
    )
    (net (code "17") (name "G1") (class "Default")
      (node (ref "Q10") (pin "G") (pinfunction "G_G") (pintype "passive"))
      (node (ref "Q11") (pin "G") (pinfunction "G_G") (pintype "passive"))
      (node (ref "U5") (pin "G1") (pinfunction "G1_G1") (pintype "bidirectional"))
    )
    (net (code "18") (name "G2") (class "Default")
      (node (ref "Q12") (pin "G") (pinfunction "G_G") (pintype "passive"))
      (node (ref "Q13") (pin "G") (pinfunction "G_G") (pintype "passive"))
      (node (ref "U5") (pin "G2") (pinfunction "G2_G2") (pintype "bidirectional"))
    )
    (net (code "19") (name "GATE1") (class "Default")
      (node (ref "Q17") (pin "1") (pinfunction "G_1") (pintype "passive"))
      (node (ref "U6") (pin "5") (pinfunction "GATE_5") (pintype "passive"))
    )
    (net (code "20") (name "GATE2") (class "Default")
      (node (ref "Q18") (pin "1") (pinfunction "G_1") (pintype "passive"))
      (node (ref "U7") (pin "5") (pinfunction "GATE_5") (pintype "passive"))
    )
    (net (code "21") (name "GATE3") (class "Default")
      (node (ref "Q19") (pin "1") (pinfunction "G_1") (pintype "passive"))
      (node (ref "U8") (pin "5") (pinfunction "GATE_5") (pintype "passive"))
    )
    (net (code "22") (name "GATE4") (class "Default")
      (node (ref "Q20") (pin "1") (pinfunction "G_1") (pintype "passive"))
      (node (ref "U10") (pin "5") (pinfunction "GATE_5") (pintype "passive"))
    )
    (net (code "23") (name "GATE5") (class "Default")
      (node (ref "R46") (pin "1") (pinfunction "1_1") (pintype "passive"))
      (node (ref "U12") (pin "7") (pinfunction "HO_7") (pintype "bidirectional"))
    )
    (net (code "24") (name "GND") (class "Default")
      (node (ref "3V1") (pin "C") (pinfunction "C_C") (pintype "passive"))
      (node (ref "C1") (pin "2") (pinfunction "2_2") (pintype "passive"))
      (node (ref "C10") (pin "2") (pinfunction "2_2") (pintype "passive"))
      (node (ref "C13") (pin "2") (pinfunction "2_2") (pintype "passive"))
      (node (ref "C14") (pin "2") (pinfunction "2_2") (pintype "passive"))
      (node (ref "C15") (pin "2") (pinfunction "2_2") (pintype "passive"))
      (node (ref "C16") (pin "2") (pinfunction "2_2") (pintype "passive"))
      (node (ref "C17") (pin "2") (pinfunction "2_2") (pintype "passive"))
      (node (ref "C2") (pin "2") (pinfunction "2_2") (pintype "passive"))
      (node (ref "C3") (pin "2") (pinfunction "2_2") (pintype "passive"))
      (node (ref "C4") (pin "2") (pinfunction "2_2") (pintype "passive"))
      (node (ref "C5") (pin "2") (pinfunction "2_2") (pintype "passive"))
      (node (ref "C6") (pin "2") (pinfunction "2_2") (pintype "passive"))
      (node (ref "C7") (pin "2") (pinfunction "2_2") (pintype "passive"))
      (node (ref "C8") (pin "2") (pinfunction "2_2") (pintype "passive"))
      (node (ref "C9") (pin "2") (pinfunction "2_2") (pintype "passive"))
      (node (ref "CON1") (pin "2") (pinfunction "S_2") (pintype "passive"))
      (node (ref "CON2") (pin "P$4") (pinfunction "S_P$4") (pintype "passive"))
      (node (ref "CON2") (pin "P$5") (pinfunction "S_P$5") (pintype "passive"))
      (node (ref "CON3") (pin "P$4") (pinfunction "S_P$4") (pintype "passive"))
      (node (ref "CON3") (pin "P$5") (pinfunction "S_P$5") (pintype "passive"))
      (node (ref "DANGER1") (pin "C") (pinfunction "C_C") (pintype "passive"))
      (node (ref "J1") (pin "1") (pinfunction "KL_1") (pintype "passive"))
      (node (ref "J16") (pin "2") (pinfunction "KL1_2") (pintype "passive"))
      (node (ref "J9") (pin "1") (pinfunction "KL_1") (pintype "passive"))
      (node (ref "JP1") (pin "2") (pinfunction "2_2") (pintype "passive"))
      (node (ref "JP2") (pin "3") (pinfunction "3_3") (pintype "passive"))
      (node (ref "JP6") (pin "1") (pinfunction "1_1") (pintype "passive"))
      (node (ref "JP6") (pin "2") (pinfunction "2_2") (pintype "passive"))
      (node (ref "Q15") (pin "2D") (pinfunction "D_2D") (pintype "passive"))
      (node (ref "Q4") (pin "2D") (pinfunction "D_2D") (pintype "passive"))
      (node (ref "Q5") (pin "2D") (pinfunction "D_2D") (pintype "passive"))
      (node (ref "Q6") (pin "2D") (pinfunction "D_2D") (pintype "passive"))
      (node (ref "R18") (pin "1") (pinfunction "1_1") (pintype "passive"))
      (node (ref "R24") (pin "1") (pinfunction "1_1") (pintype "passive"))
      (node (ref "R27") (pin "1") (pinfunction "1_1") (pintype "passive"))
      (node (ref "R28") (pin "1") (pinfunction "1_1") (pintype "passive"))
      (node (ref "U1") (pin "3") (pinfunction "GND_3") (pintype "power_in"))
      (node (ref "U1") (pin "5") (pinfunction "A0_5") (pintype "input"))
      (node (ref "U10") (pin "2") (pinfunction "GND_2") (pintype "power_in"))
      (node (ref "U12") (pin "3") (pinfunction "LIN_3") (pintype "bidirectional"))
      (node (ref "U12") (pin "4") (pinfunction "GND_4") (pintype "bidirectional"))
      (node (ref "U2") (pin "3") (pinfunction "GND_3") (pintype "power_in"))
      (node (ref "U3") (pin "GND") (pinfunction "GND_GND") (pintype "power_in"))
      (node (ref "U4") (pin "2") (pinfunction "GND_2") (pintype "bidirectional"))
      (node (ref "U5") (pin "GND@1") (pinfunction "GND_GND@1") (pintype "power_in"))
      (node (ref "U5") (pin "GND@2") (pinfunction "GND_GND@2") (pintype "power_in"))
      (node (ref "U6") (pin "2") (pinfunction "GND_2") (pintype "power_in"))
      (node (ref "U7") (pin "2") (pinfunction "GND_2") (pintype "power_in"))
      (node (ref "U8") (pin "2") (pinfunction "GND_2") (pintype "power_in"))
    )
    (net (code "25") (name "HYS") (class "Default")
      (node (ref "R28") (pin "2") (pinfunction "2_2") (pintype "passive"))
      (node (ref "U5") (pin "HYS") (pinfunction "HYS_HYS") (pintype "bidirectional"))
    )
    (net (code "26") (name "IO1") (class "Default")
      (node (ref "U12") (pin "2") (pinfunction "HIN_2") (pintype "bidirectional"))
      (node (ref "U3") (pin "17/A3") (pinfunction "17/A3/T_17/A3") (pintype "bidirectional"))
    )
    (net (code "27") (name "IO2") (class "Default")
      (node (ref "U10") (pin "3") (pinfunction "OFF_3") (pintype "passive"))
      (node (ref "U3") (pin "13") (pinfunction "13/SCK/LED_13") (pintype "bidirectional"))
      (node (ref "U6") (pin "3") (pinfunction "OFF_3") (pintype "passive"))
      (node (ref "U7") (pin "3") (pinfunction "OFF_3") (pintype "passive"))
      (node (ref "U8") (pin "3") (pinfunction "OFF_3") (pintype "passive"))
    )
    (net (code "28") (name "IO3") (class "Default")
      (node (ref "R42") (pin "1") (pinfunction "1_1") (pintype "passive"))
      (node (ref "U3") (pin "15/A1") (pinfunction "15/A1/T_15/A1") (pintype "bidirectional"))
      (node (ref "U7") (pin "1") (pinfunction "NFGD_1") (pintype "passive"))
    )
    (net (code "29") (name "IO4") (class "Default")
      (node (ref "R41") (pin "1") (pinfunction "1_1") (pintype "passive"))
      (node (ref "U3") (pin "12") (pinfunction "12/MISO_12") (pintype "bidirectional"))
      (node (ref "U8") (pin "1") (pinfunction "NFGD_1") (pintype "passive"))
    )
    (net (code "30") (name "IO5") (class "Default")
      (node (ref "R43") (pin "1") (pinfunction "1_1") (pintype "passive"))
      (node (ref "U3") (pin "16/A2") (pinfunction "16/A2/T_16/A2") (pintype "bidirectional"))
      (node (ref "U6") (pin "1") (pinfunction "NFGD_1") (pintype "passive"))
    )
    (net (code "31") (name "IO6") (class "Default")
      (node (ref "R44") (pin "1") (pinfunction "1_1") (pintype "passive"))
      (node (ref "U10") (pin "1") (pinfunction "NFGD_1") (pintype "passive"))
      (node (ref "U3") (pin "14/A0") (pinfunction "14/A0_14/A0") (pintype "bidirectional"))
    )
    (net (code "32") (name "LED_D") (class "Default")
      (node (ref "R36") (pin "1") (pinfunction "1_1") (pintype "passive"))
      (node (ref "U3") (pin "23/A9") (pinfunction "23/A9/T/PWM_23/A9") (pintype "bidirectional"))
    )
    (net (code "33") (name "MOTOR1") (class "Default")
      (node (ref "C14") (pin "1") (pinfunction "1_1") (pintype "passive"))
      (node (ref "Q17") (pin "3") (pinfunction "S_3") (pintype "passive"))
      (node (ref "R8") (pin "P$1") (pinfunction "1_P$1") (pintype "passive"))
      (node (ref "U1") (pin "11") (pinfunction "IN-1_11") (pintype "input"))
      (node (ref "U6") (pin "4") (pinfunction "IN_4") (pintype "input"))
    )
    (net (code "34") (name "MOTOR2") (class "Default")
      (node (ref "C13") (pin "1") (pinfunction "1_1") (pintype "passive"))
      (node (ref "Q18") (pin "3") (pinfunction "S_3") (pintype "passive"))
      (node (ref "R4") (pin "P$1") (pinfunction "1_P$1") (pintype "passive"))
      (node (ref "U1") (pin "14") (pinfunction "IN-2_14") (pintype "input"))
      (node (ref "U7") (pin "4") (pinfunction "IN_4") (pintype "input"))
    )
    (net (code "35") (name "MOTOR3") (class "Default")
      (node (ref "C15") (pin "1") (pinfunction "1_1") (pintype "passive"))
      (node (ref "Q19") (pin "3") (pinfunction "S_3") (pintype "passive"))
      (node (ref "R13") (pin "P$1") (pinfunction "1_P$1") (pintype "passive"))
      (node (ref "U2") (pin "11") (pinfunction "IN-1_11") (pintype "input"))
      (node (ref "U8") (pin "4") (pinfunction "IN_4") (pintype "input"))
    )
    (net (code "36") (name "MOTOR4") (class "Default")
      (node (ref "C16") (pin "1") (pinfunction "1_1") (pintype "passive"))
      (node (ref "Q20") (pin "3") (pinfunction "S_3") (pintype "passive"))
      (node (ref "R35") (pin "P$1") (pinfunction "1_P$1") (pintype "passive"))
      (node (ref "U1") (pin "1") (pinfunction "IN-3_1") (pintype "input"))
      (node (ref "U10") (pin "4") (pinfunction "IN_4") (pintype "input"))
    )
    (net (code "37") (name "NIU") (class "Default")
      (node (ref "C6") (pin "1") (pinfunction "1_1") (pintype "passive"))
      (node (ref "U5") (pin "!SHDN") (pinfunction "~{SHDN}_!SHDN") (pintype "bidirectional"))
      (node (ref "U5") (pin "EN") (pinfunction "EN_EN") (pintype "bidirectional"))
      (node (ref "U5") (pin "INTVCC") (pinfunction "INTVCC_INTVCC") (pintype "bidirectional"))
    )
    (net (code "38") (name "Net-(3V1-PadA)") (class "Default")
      (node (ref "3V1") (pin "A") (pinfunction "A_A") (pintype "passive"))
      (node (ref "R37") (pin "1") (pinfunction "1_1") (pintype "passive"))
    )
    (net (code "39") (name "Net-(C5-Pad1)") (class "Default")
      (node (ref "C5") (pin "1") (pinfunction "1_1") (pintype "passive"))
      (node (ref "U5") (pin "TMR") (pinfunction "TMR_TMR") (pintype "bidirectional"))
    )
    (net (code "40") (name "Net-(CON2A-S)") (class "Default")
      (node (ref "CON2") (pin "P$1") (pinfunction "S_P$1") (pintype "passive"))
      (node (ref "CON3") (pin "P$1") (pinfunction "S_P$1") (pintype "passive"))
    )
    (net (code "41") (name "Net-(CON2B-S)") (class "Default")
      (node (ref "CON2") (pin "P$2") (pinfunction "S_P$2") (pintype "passive"))
      (node (ref "CON3") (pin "P$2") (pinfunction "S_P$2") (pintype "passive"))
      (node (ref "U4") (pin "6") (pinfunction "CANL_6") (pintype "bidirectional"))
    )
    (net (code "42") (name "Net-(CON2C-S)") (class "Default")
      (node (ref "CON2") (pin "P$3") (pinfunction "S_P$3") (pintype "passive"))
      (node (ref "CON3") (pin "P$3") (pinfunction "S_P$3") (pintype "passive"))
      (node (ref "U4") (pin "7") (pinfunction "CANH_7") (pintype "bidirectional"))
    )
    (net (code "43") (name "Net-(D1-A)") (class "Default")
      (node (ref "D1") (pin "P$2") (pinfunction "A_P$2") (pintype "passive"))
      (node (ref "J4") (pin "1") (pinfunction "KL_1") (pintype "passive"))
      (node (ref "Q4") (pin "3S") (pinfunction "S_3S") (pintype "passive"))
      (node (ref "R21") (pin "1") (pinfunction "1_1") (pintype "passive"))
      (node (ref "R9") (pin "1") (pinfunction "1_1") (pintype "passive"))
    )
    (net (code "44") (name "Net-(D1-C)") (class "Default")
      (node (ref "D1") (pin "P$1") (pinfunction "C_P$1") (pintype "passive"))
      (node (ref "Q4") (pin "1G") (pinfunction "G_1G") (pintype "passive"))
      (node (ref "R5") (pin "1") (pinfunction "1_1") (pintype "passive"))
      (node (ref "R9") (pin "2") (pinfunction "2_2") (pintype "passive"))
    )
    (net (code "45") (name "Net-(D2-A)") (class "Default")
      (node (ref "D2") (pin "P$2") (pinfunction "A_P$2") (pintype "passive"))
      (node (ref "J3") (pin "1") (pinfunction "KL_1") (pintype "passive"))
      (node (ref "Q5") (pin "3S") (pinfunction "S_3S") (pintype "passive"))
      (node (ref "R10") (pin "1") (pinfunction "1_1") (pintype "passive"))
      (node (ref "R19") (pin "1") (pinfunction "1_1") (pintype "passive"))
    )
    (net (code "46") (name "Net-(D2-C)") (class "Default")
      (node (ref "D2") (pin "P$1") (pinfunction "C_P$1") (pintype "passive"))
      (node (ref "Q5") (pin "1G") (pinfunction "G_1G") (pintype "passive"))
      (node (ref "R10") (pin "2") (pinfunction "2_2") (pintype "passive"))
      (node (ref "R6") (pin "1") (pinfunction "1_1") (pintype "passive"))
    )
    (net (code "47") (name "Net-(D3-A)") (class "Default")
      (node (ref "D3") (pin "P$2") (pinfunction "A_P$2") (pintype "passive"))
      (node (ref "J2") (pin "1") (pinfunction "KL_1") (pintype "passive"))
      (node (ref "Q6") (pin "3S") (pinfunction "S_3S") (pintype "passive"))
      (node (ref "R11") (pin "1") (pinfunction "1_1") (pintype "passive"))
      (node (ref "R20") (pin "1") (pinfunction "1_1") (pintype "passive"))
    )
    (net (code "48") (name "Net-(D3-C)") (class "Default")
      (node (ref "D3") (pin "P$1") (pinfunction "C_P$1") (pintype "passive"))
      (node (ref "Q6") (pin "1G") (pinfunction "G_1G") (pintype "passive"))
      (node (ref "R11") (pin "2") (pinfunction "2_2") (pintype "passive"))
      (node (ref "R7") (pin "1") (pinfunction "1_1") (pintype "passive"))
    )
    (net (code "49") (name "Net-(D4-A)") (class "Default")
      (node (ref "D4") (pin "P$2") (pinfunction "A_P$2") (pintype "passive"))
      (node (ref "J10") (pin "1") (pinfunction "KL_1") (pintype "passive"))
      (node (ref "Q15") (pin "3S") (pinfunction "S_3S") (pintype "passive"))
      (node (ref "R31") (pin "1") (pinfunction "1_1") (pintype "passive"))
      (node (ref "R32") (pin "1") (pinfunction "1_1") (pintype "passive"))
    )
    (net (code "50") (name "Net-(D4-C)") (class "Default")
      (node (ref "D4") (pin "P$1") (pinfunction "C_P$1") (pintype "passive"))
      (node (ref "Q15") (pin "1G") (pinfunction "G_1G") (pintype "passive"))
      (node (ref "R32") (pin "2") (pinfunction "2_2") (pintype "passive"))
      (node (ref "R33") (pin "1") (pinfunction "1_1") (pintype "passive"))
    )
    (net (code "51") (name "Net-(D5-PadA)") (class "Default")
      (node (ref "D5") (pin "A") (pinfunction "A_A") (pintype "passive"))
      (node (ref "R45") (pin "2") (pinfunction "2_2") (pintype "passive"))
    )
    (net (code "52") (name "Net-(DANGER1-PadA)") (class "Default")
      (node (ref "DANGER1") (pin "A") (pinfunction "A_A") (pintype "passive"))
      (node (ref "R36") (pin "2") (pinfunction "2_2") (pintype "passive"))
    )
    (net (code "53") (name "Net-(JP2-Pad2)") (class "Default")
      (node (ref "JP2") (pin "2") (pinfunction "2_2") (pintype "passive"))
      (node (ref "JP3") (pin "2") (pinfunction "2_2") (pintype "passive"))
    )
    (net (code "54") (name "Net-(JP5-Pad2)") (class "Default")
      (node (ref "JP5") (pin "2") (pinfunction "2_2") (pintype "passive"))
      (node (ref "R14") (pin "1") (pinfunction "1_1") (pintype "passive"))
    )
    (net (code "55") (name "Net-(JP5-Pad4)") (class "Default")
      (node (ref "JP5") (pin "4") (pinfunction "4_4") (pintype "passive"))
      (node (ref "R15") (pin "1") (pinfunction "1_1") (pintype "passive"))
    )
    (net (code "56") (name "Net-(JP5-Pad6)") (class "Default")
      (node (ref "JP5") (pin "6") (pinfunction "6_6") (pintype "passive"))
      (node (ref "JP6") (pin "7") (pinfunction "7_7") (pintype "passive"))
      (node (ref "JP6") (pin "8") (pinfunction "8_8") (pintype "passive"))
    )
    (net (code "57") (name "Net-(LED1-PadA)") (class "Default")
      (node (ref "LED1") (pin "A") (pinfunction "A_A") (pintype "passive"))
      (node (ref "R29") (pin "1") (pinfunction "1_1") (pintype "passive"))
    )
    (net (code "58") (name "Net-(LED2-PadA)") (class "Default")
      (node (ref "LED2") (pin "A") (pinfunction "A_A") (pintype "passive"))
      (node (ref "R30") (pin "1") (pinfunction "1_1") (pintype "passive"))
    )
    (net (code "59") (name "Net-(Q1-A)") (class "Default")
      (node (ref "Q1") (pin "P$1") (pinfunction "A_P$1") (pintype "bidirectional"))
      (node (ref "R1") (pin "2") (pinfunction "2_2") (pintype "passive"))
    )
    (net (code "60") (name "Net-(Q1-C1)") (class "Default")
      (node (ref "JP1") (pin "1") (pinfunction "1_1") (pintype "passive"))
      (node (ref "JP3") (pin "1") (pinfunction "1_1") (pintype "passive"))
      (node (ref "Q1") (pin "P$2") (pinfunction "C1_P$2") (pintype "bidirectional"))
      (node (ref "Q16") (pin "P$2") (pinfunction "C1_P$2") (pintype "bidirectional"))
      (node (ref "Q2") (pin "P$2") (pinfunction "C1_P$2") (pintype "bidirectional"))
      (node (ref "Q3") (pin "P$2") (pinfunction "C1_P$2") (pintype "bidirectional"))
    )
    (net (code "61") (name "Net-(Q1-E)") (class "Default")
      (node (ref "Q1") (pin "P$3") (pinfunction "E_P$3") (pintype "bidirectional"))
      (node (ref "R5") (pin "2") (pinfunction "2_2") (pintype "passive"))
    )
    (net (code "62") (name "Net-(Q2-A)") (class "Default")
      (node (ref "Q2") (pin "P$1") (pinfunction "A_P$1") (pintype "bidirectional"))
      (node (ref "R2") (pin "2") (pinfunction "2_2") (pintype "passive"))
    )
    (net (code "63") (name "Net-(Q2-E)") (class "Default")
      (node (ref "Q2") (pin "P$3") (pinfunction "E_P$3") (pintype "bidirectional"))
      (node (ref "R6") (pin "2") (pinfunction "2_2") (pintype "passive"))
    )
    (net (code "64") (name "Net-(Q3-A)") (class "Default")
      (node (ref "Q3") (pin "P$1") (pinfunction "A_P$1") (pintype "bidirectional"))
      (node (ref "R3") (pin "2") (pinfunction "2_2") (pintype "passive"))
    )
    (net (code "65") (name "Net-(Q3-E)") (class "Default")
      (node (ref "Q3") (pin "P$3") (pinfunction "E_P$3") (pintype "bidirectional"))
      (node (ref "R7") (pin "2") (pinfunction "2_2") (pintype "passive"))
    )
    (net (code "66") (name "Net-(Q7-PadG)") (class "Default")
      (node (ref "Q7") (pin "G") (pinfunction "G_G") (pintype "passive"))
      (node (ref "R19") (pin "2") (pinfunction "2_2") (pintype "passive"))
    )
    (net (code "67") (name "Net-(Q8-PadG)") (class "Default")
      (node (ref "Q8") (pin "G") (pinfunction "G_G") (pintype "passive"))
      (node (ref "R31") (pin "2") (pinfunction "2_2") (pintype "passive"))
    )
    (net (code "68") (name "Net-(Q9-PadG)") (class "Default")
      (node (ref "Q9") (pin "G") (pinfunction "G_G") (pintype "passive"))
      (node (ref "R21") (pin "2") (pinfunction "2_2") (pintype "passive"))
    )
    (net (code "69") (name "Net-(Q14-PadG)") (class "Default")
      (node (ref "Q14") (pin "G") (pinfunction "G_G") (pintype "passive"))
      (node (ref "R20") (pin "2") (pinfunction "2_2") (pintype "passive"))
    )
    (net (code "70") (name "Net-(Q16-A)") (class "Default")
      (node (ref "Q16") (pin "P$1") (pinfunction "A_P$1") (pintype "bidirectional"))
      (node (ref "R34") (pin "2") (pinfunction "2_2") (pintype "passive"))
    )
    (net (code "71") (name "Net-(Q16-E)") (class "Default")
      (node (ref "Q16") (pin "P$3") (pinfunction "E_P$3") (pintype "bidirectional"))
      (node (ref "R33") (pin "2") (pinfunction "2_2") (pintype "passive"))
    )
    (net (code "72") (name "Net-(Q21-G)") (class "Default")
      (node (ref "Q21") (pin "4") (pinfunction "G_4") (pintype "passive"))
      (node (ref "R46") (pin "2") (pinfunction "2_2") (pintype "passive"))
    )
    (net (code "73") (name "Net-(U4-RXD)") (class "Default")
      (node (ref "R17") (pin "2") (pinfunction "2_2") (pintype "passive"))
      (node (ref "U4") (pin "4") (pinfunction "RXD_4") (pintype "bidirectional"))
    )
    (net (code "74") (name "Net-(U4-STB)") (class "Default")
      (node (ref "R18") (pin "2") (pinfunction "2_2") (pintype "passive"))
      (node (ref "U4") (pin "8") (pinfunction "STB_8") (pintype "bidirectional"))
    )
    (net (code "75") (name "Net-(U4-TXD)") (class "Default")
      (node (ref "R16") (pin "2") (pinfunction "2_2") (pintype "passive"))
      (node (ref "U4") (pin "1") (pinfunction "TXD_1") (pintype "bidirectional"))
    )
    (net (code "76") (name "Net-(U5-~{VALID1})") (class "Default")
      (node (ref "LED2") (pin "C") (pinfunction "C_C") (pintype "passive"))
      (node (ref "U5") (pin "!VALID1") (pinfunction "~{VALID1}_!VALID1") (pintype "bidirectional"))
    )
    (net (code "77") (name "Net-(U5-~{VALID2})") (class "Default")
      (node (ref "LED1") (pin "C") (pinfunction "C_C") (pintype "passive"))
      (node (ref "U5") (pin "!VALID2") (pinfunction "~{VALID2}_!VALID2") (pintype "bidirectional"))
    )
    (net (code "78") (name "Net-(U12-VB)") (class "Default")
      (node (ref "C18") (pin "1") (pinfunction "1_1") (pintype "passive"))
      (node (ref "D5") (pin "C") (pinfunction "C_C") (pintype "passive"))
      (node (ref "U12") (pin "8") (pinfunction "VB_8") (pintype "bidirectional"))
    )
    (net (code "79") (name "Net-(U12-VS)") (class "Default")
      (node (ref "C18") (pin "2") (pinfunction "2_2") (pintype "passive"))
      (node (ref "U12") (pin "6") (pinfunction "VS_6") (pintype "bidirectional"))
    )
    (net (code "80") (name "OV1") (class "Default")
      (node (ref "R23") (pin "1") (pinfunction "1_1") (pintype "passive"))
      (node (ref "R24") (pin "2") (pinfunction "2_2") (pintype "passive"))
      (node (ref "U5") (pin "OV1") (pinfunction "OV1_OV1") (pintype "bidirectional"))
    )
    (net (code "81") (name "OV2") (class "Default")
      (node (ref "R26") (pin "1") (pinfunction "1_1") (pintype "passive"))
      (node (ref "R27") (pin "2") (pinfunction "2_2") (pintype "passive"))
      (node (ref "U5") (pin "OV2") (pinfunction "OV2_OV2") (pintype "bidirectional"))
    )
    (net (code "82") (name "POWER_BOARD") (class "Default")
      (node (ref "C17") (pin "1") (pinfunction "1_1") (pintype "passive"))
      (node (ref "Q21") (pin "5") (pinfunction "D_5") (pintype "passive"))
      (node (ref "Q21") (pin "6") (pinfunction "D_6") (pintype "passive"))
      (node (ref "Q21") (pin "7") (pinfunction "D_7") (pintype "passive"))
      (node (ref "Q21") (pin "8") (pinfunction "D_8") (pintype "passive"))
      (node (ref "R12") (pin "P$1") (pinfunction "1_P$1") (pintype "passive"))
      (node (ref "R45") (pin "1") (pinfunction "1_1") (pintype "passive"))
      (node (ref "U12") (pin "1") (pinfunction "VCC_1") (pintype "bidirectional"))
      (node (ref "U2") (pin "1") (pinfunction "IN-3_1") (pintype "input"))
      (node (ref "U2") (pin "14") (pinfunction "IN-2_14") (pintype "input"))
    )
    (net (code "83") (name "PV_OUT") (class "Default")
      (node (ref "U1") (pin "10") (pinfunction "PV_10") (pintype "output"))
      (node (ref "U2") (pin "10") (pinfunction "PV_10") (pintype "output"))
      (node (ref "U3") (pin "7") (pinfunction "7/RX3_7") (pintype "bidirectional"))
    )
    (net (code "84") (name "SCL") (class "Default")
      (node (ref "JP6") (pin "5") (pinfunction "5_5") (pintype "passive"))
      (node (ref "JP6") (pin "6") (pinfunction "6_6") (pintype "passive"))
      (node (ref "R14") (pin "2") (pinfunction "2_2") (pintype "passive"))
      (node (ref "U1") (pin "6") (pinfunction "SCL_6") (pintype "input"))
      (node (ref "U2") (pin "6") (pinfunction "SCL_6") (pintype "input"))
      (node (ref "U3") (pin "19/A5") (pinfunction "19/A5/T/SCL0_19/A5") (pintype "bidirectional"))
    )
    (net (code "85") (name "SDA") (class "Default")
      (node (ref "JP6") (pin "3") (pinfunction "3_3") (pintype "passive"))
      (node (ref "JP6") (pin "4") (pinfunction "4_4") (pintype "passive"))
      (node (ref "R15") (pin "2") (pinfunction "2_2") (pintype "passive"))
      (node (ref "U1") (pin "7") (pinfunction "SDA_7") (pintype "bidirectional"))
      (node (ref "U2") (pin "7") (pinfunction "SDA_7") (pintype "bidirectional"))
      (node (ref "U3") (pin "18/A4") (pinfunction "18/A4/T/SDA0_18/A4") (pintype "bidirectional"))
    )
    (net (code "86") (name "TC_OUT") (class "Default")
      (node (ref "U1") (pin "13") (pinfunction "TC_13") (pintype "output"))
      (node (ref "U2") (pin "13") (pinfunction "TC_13") (pintype "output"))
      (node (ref "U3") (pin "8") (pinfunction "8/TX3_8") (pintype "bidirectional"))
    )
    (net (code "87") (name "UV1") (class "Default")
      (node (ref "R22") (pin "1") (pinfunction "1_1") (pintype "passive"))
      (node (ref "R23") (pin "2") (pinfunction "2_2") (pintype "passive"))
      (node (ref "U5") (pin "UV1") (pinfunction "UV1_UV1") (pintype "bidirectional"))
    )
    (net (code "88") (name "UV2") (class "Default")
      (node (ref "R25") (pin "1") (pinfunction "1_1") (pintype "passive"))
      (node (ref "R26") (pin "2") (pinfunction "2_2") (pintype "passive"))
      (node (ref "U5") (pin "UV2") (pinfunction "UV2_UV2") (pintype "bidirectional"))
    )
    (net (code "89") (name "VIN") (class "Default")
      (node (ref "C4") (pin "1") (pinfunction "1_1") (pintype "passive"))
      (node (ref "JP4") (pin "1") (pinfunction "1_1") (pintype "passive"))
      (node (ref "U3") (pin "VIN") (pinfunction "VIN_VIN") (pintype "power_in"))
      (node (ref "U4") (pin "3") (pinfunction "VCC_3") (pintype "bidirectional"))
    )
    (net (code "90") (name "VOUT") (class "Default")
      (node (ref "J16") (pin "1") (pinfunction "KL_1") (pintype "passive"))
      (node (ref "Q17") (pin "2") (pinfunction "D_2") (pintype "passive"))
      (node (ref "Q18") (pin "2") (pinfunction "D_2") (pintype "passive"))
      (node (ref "Q19") (pin "2") (pinfunction "D_2") (pintype "passive"))
      (node (ref "Q20") (pin "2") (pinfunction "D_2") (pintype "passive"))
      (node (ref "Q21") (pin "1") (pinfunction "S_1") (pintype "passive"))
      (node (ref "Q21") (pin "2") (pinfunction "S_2") (pintype "passive"))
      (node (ref "Q21") (pin "3") (pinfunction "S_3") (pintype "passive"))
      (node (ref "U10") (pin "6") (pinfunction "OUT_6") (pintype "output"))
      (node (ref "U6") (pin "6") (pinfunction "OUT_6") (pintype "output"))
      (node (ref "U7") (pin "6") (pinfunction "OUT_6") (pintype "output"))
      (node (ref "U8") (pin "6") (pinfunction "OUT_6") (pintype "output"))
    )
    (net (code "91") (name "VS1") (class "Default")
      (node (ref "C9") (pin "1") (pinfunction "1_1") (pintype "passive"))
      (node (ref "Q10") (pin "S@1") (pinfunction "S_S@1") (pintype "passive"))
      (node (ref "Q10") (pin "S@2") (pinfunction "S_S@2") (pintype "passive"))
      (node (ref "Q10") (pin "S@3") (pinfunction "S_S@3") (pintype "passive"))
      (node (ref "Q11") (pin "S@1") (pinfunction "S_S@1") (pintype "passive"))
      (node (ref "Q11") (pin "S@2") (pinfunction "S_S@2") (pintype "passive"))
      (node (ref "Q11") (pin "S@3") (pinfunction "S_S@3") (pintype "passive"))
      (node (ref "U5") (pin "VS1") (pinfunction "VS1_VS1") (pintype "bidirectional"))
    )
    (net (code "92") (name "VS2") (class "Default")
      (node (ref "C10") (pin "1") (pinfunction "1_1") (pintype "passive"))
      (node (ref "Q12") (pin "S@1") (pinfunction "S_S@1") (pintype "passive"))
      (node (ref "Q12") (pin "S@2") (pinfunction "S_S@2") (pintype "passive"))
      (node (ref "Q12") (pin "S@3") (pinfunction "S_S@3") (pintype "passive"))
      (node (ref "Q13") (pin "S@1") (pinfunction "S_S@1") (pintype "passive"))
      (node (ref "Q13") (pin "S@2") (pinfunction "S_S@2") (pintype "passive"))
      (node (ref "Q13") (pin "S@3") (pinfunction "S_S@3") (pintype "passive"))
      (node (ref "U5") (pin "VS2") (pinfunction "VS2_VS2") (pintype "bidirectional"))
    )
    (net (code "93") (name "WALL") (class "Default")
      (node (ref "C7") (pin "1") (pinfunction "1_1") (pintype "passive"))
      (node (ref "J9") (pin "2") (pinfunction "KL1_2") (pintype "passive"))
      (node (ref "Q10") (pin "D@1") (pinfunction "D_D@1") (pintype "passive"))
      (node (ref "Q10") (pin "D@2") (pinfunction "D_D@2") (pintype "passive"))
      (node (ref "Q10") (pin "D@3") (pinfunction "D_D@3") (pintype "passive"))
      (node (ref "Q10") (pin "D@4") (pinfunction "D_D@4") (pintype "passive"))
      (node (ref "Q10") (pin "D@5") (pinfunction "D_D@5") (pintype "passive"))
      (node (ref "R22") (pin "2") (pinfunction "2_2") (pintype "passive"))
      (node (ref "U5") (pin "V1") (pinfunction "V1_V1") (pintype "bidirectional"))
    )
    (net (code "94") (name "WARNING_OUT") (class "Default")
      (node (ref "U1") (pin "8") (pinfunction "WARNING_8") (pintype "output"))
      (node (ref "U2") (pin "8") (pinfunction "WARNING_8") (pintype "output"))
      (node (ref "U3") (pin "10") (pinfunction "10/TX2/PWM_10") (pintype "bidirectional"))
    )
    (net (code "95") (name "unconnected-(U2-IN+3-Pad2)") (class "Default")
      (node (ref "U2") (pin "2") (pinfunction "IN+3_2") (pintype "input"))
    )
    (net (code "96") (name "unconnected-(U3-0{slash}RX1{slash}T-Pad0)") (class "Default")
      (node (ref "U3") (pin "0") (pinfunction "0/RX1/T_0") (pintype "bidirectional"))
    )
    (net (code "97") (name "unconnected-(U3-1{slash}TX1{slash}T-Pad1)") (class "Default")
      (node (ref "U3") (pin "1") (pinfunction "1/TX1/T_1") (pintype "bidirectional"))
    )
    (net (code "98") (name "unconnected-(U3-5{slash}PWM-Pad5)") (class "Default")
      (node (ref "U3") (pin "5") (pinfunction "5/PWM_5") (pintype "bidirectional"))
    )
    (net (code "99") (name "unconnected-(U3-6{slash}PWM-Pad6)") (class "Default")
      (node (ref "U3") (pin "6") (pinfunction "6/PWM_6") (pintype "bidirectional"))
    )
    (net (code "100") (name "unconnected-(U3-11{slash}MOSI-Pad11)") (class "Default")
      (node (ref "U3") (pin "11") (pinfunction "11/MOSI_11") (pintype "bidirectional"))
    )
    (net (code "101") (name "unconnected-(U3-20{slash}A6{slash}PWM-Pad20{slash}A6)") (class "Default")
      (node (ref "U3") (pin "20/A6") (pinfunction "20/A6/PWM_20/A6") (pintype "bidirectional"))
    )
    (net (code "102") (name "unconnected-(U3-21{slash}A7{slash}PWM-Pad21{slash}A7)") (class "Default")
      (node (ref "U3") (pin "21/A7") (pinfunction "21/A7/PWM_21/A7") (pintype "bidirectional"))
    )
    (net (code "103") (name "unconnected-(U3-22{slash}A8{slash}T{slash}PWM-Pad22{slash}A8)") (class "Default")
      (node (ref "U3") (pin "22/A8") (pinfunction "22/A8/T/PWM_22/A8") (pintype "bidirectional"))
    )
    (net (code "104") (name "unconnected-(U3-Pad2)") (class "Default")
      (node (ref "U3") (pin "2") (pinfunction "2_2") (pintype "bidirectional"))
    )
    (net (code "105") (name "unconnected-(U5-PadCAS)") (class "Default")
      (node (ref "U5") (pin "CAS") (pinfunction "CAS_CAS") (pintype "bidirectional"))
    )
    (net (code "106") (name "unconnected-(U12-LO-Pad5)") (class "Default")
      (node (ref "U12") (pin "5") (pinfunction "LO_5") (pintype "bidirectional"))
    )
  )
)
